# CANTensegrityBoard.net
KiCad netlist of a schematic drawn in EAGLE
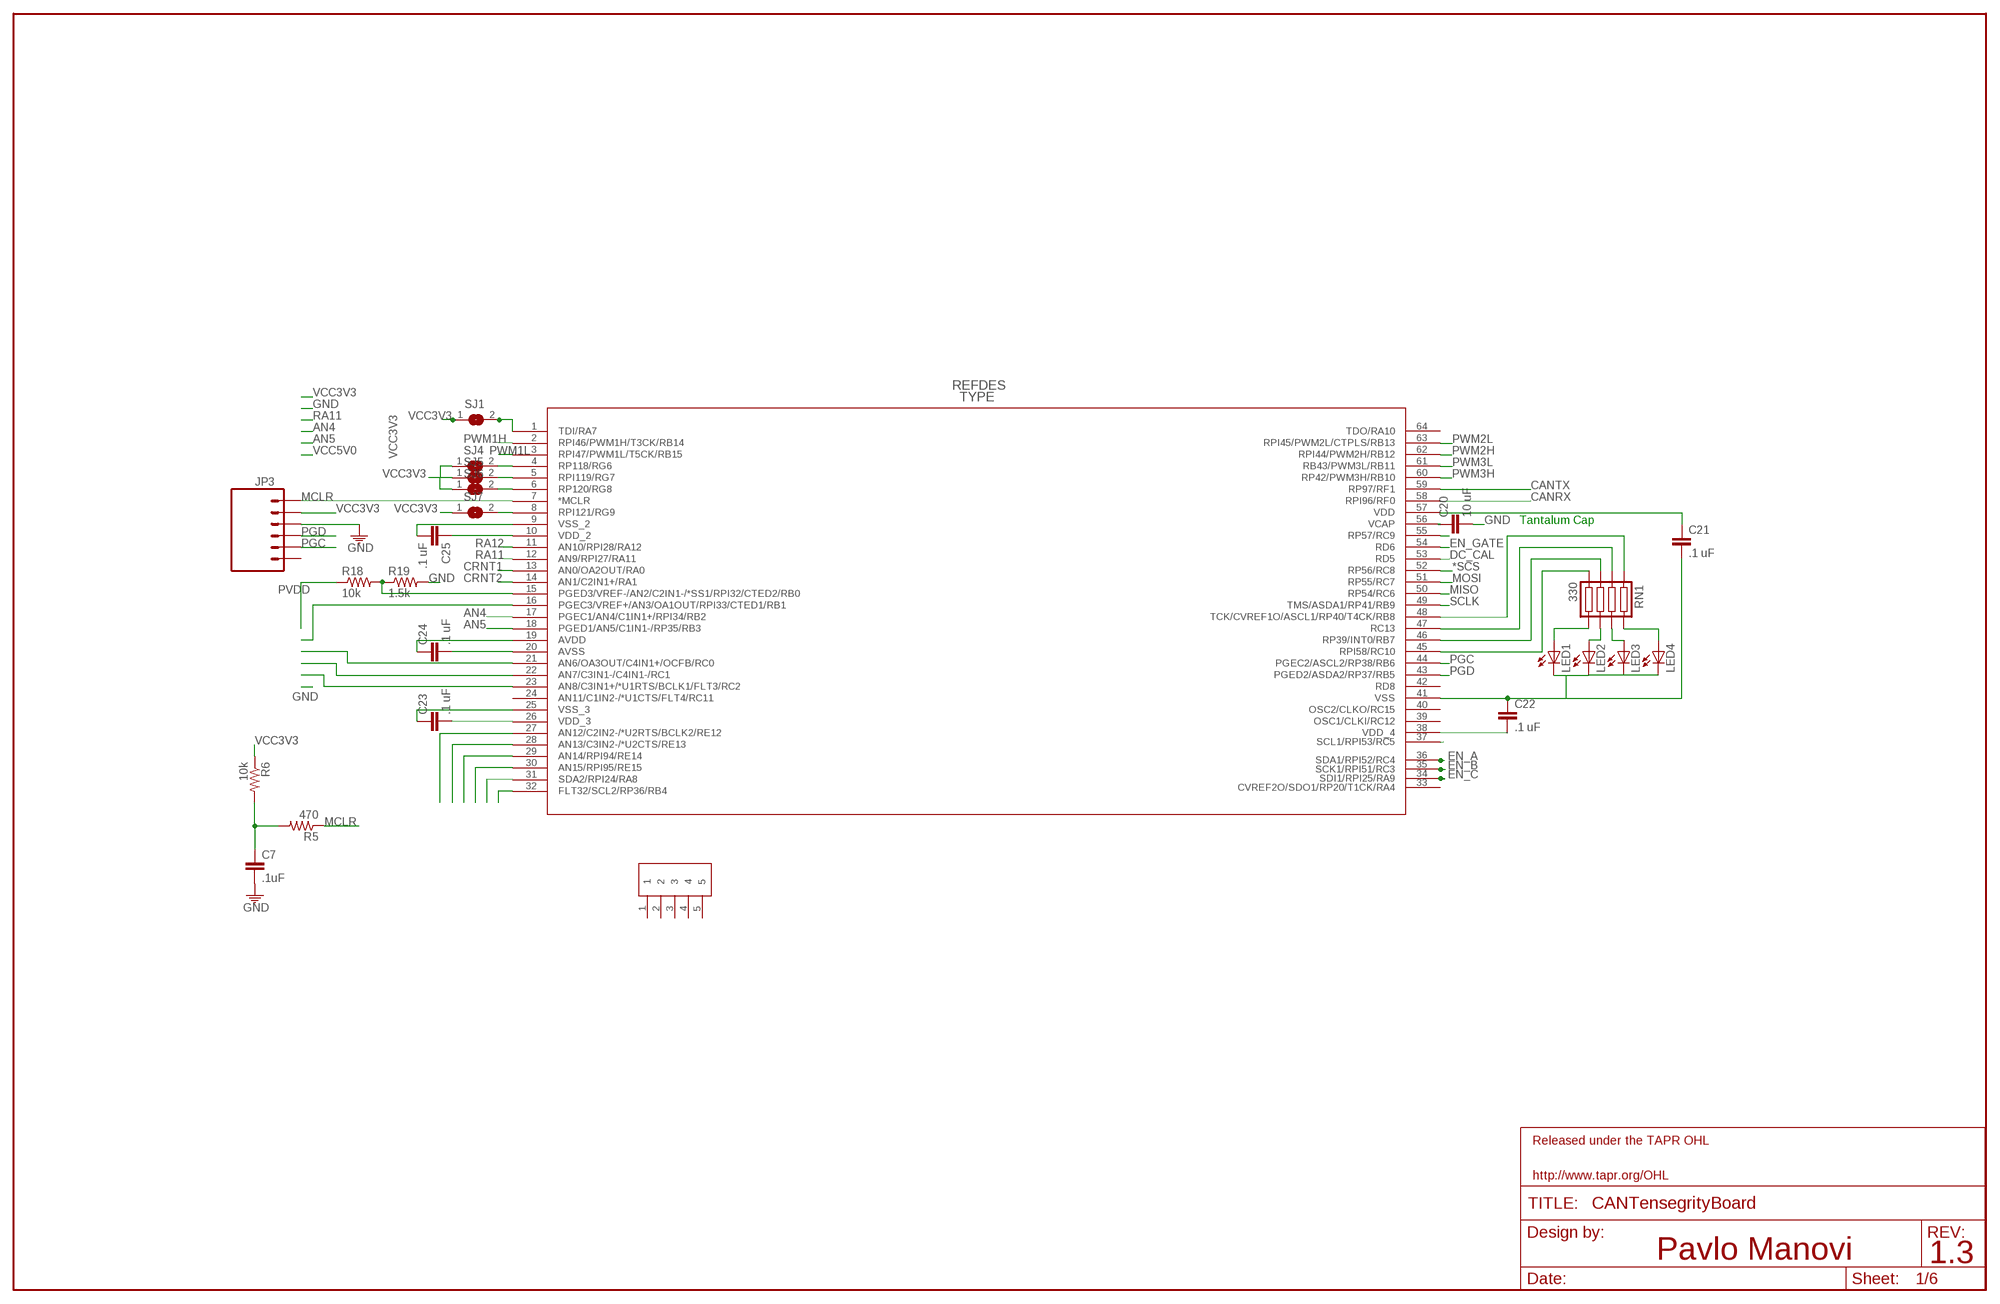
[diagram p0: schematic, sheet 1]
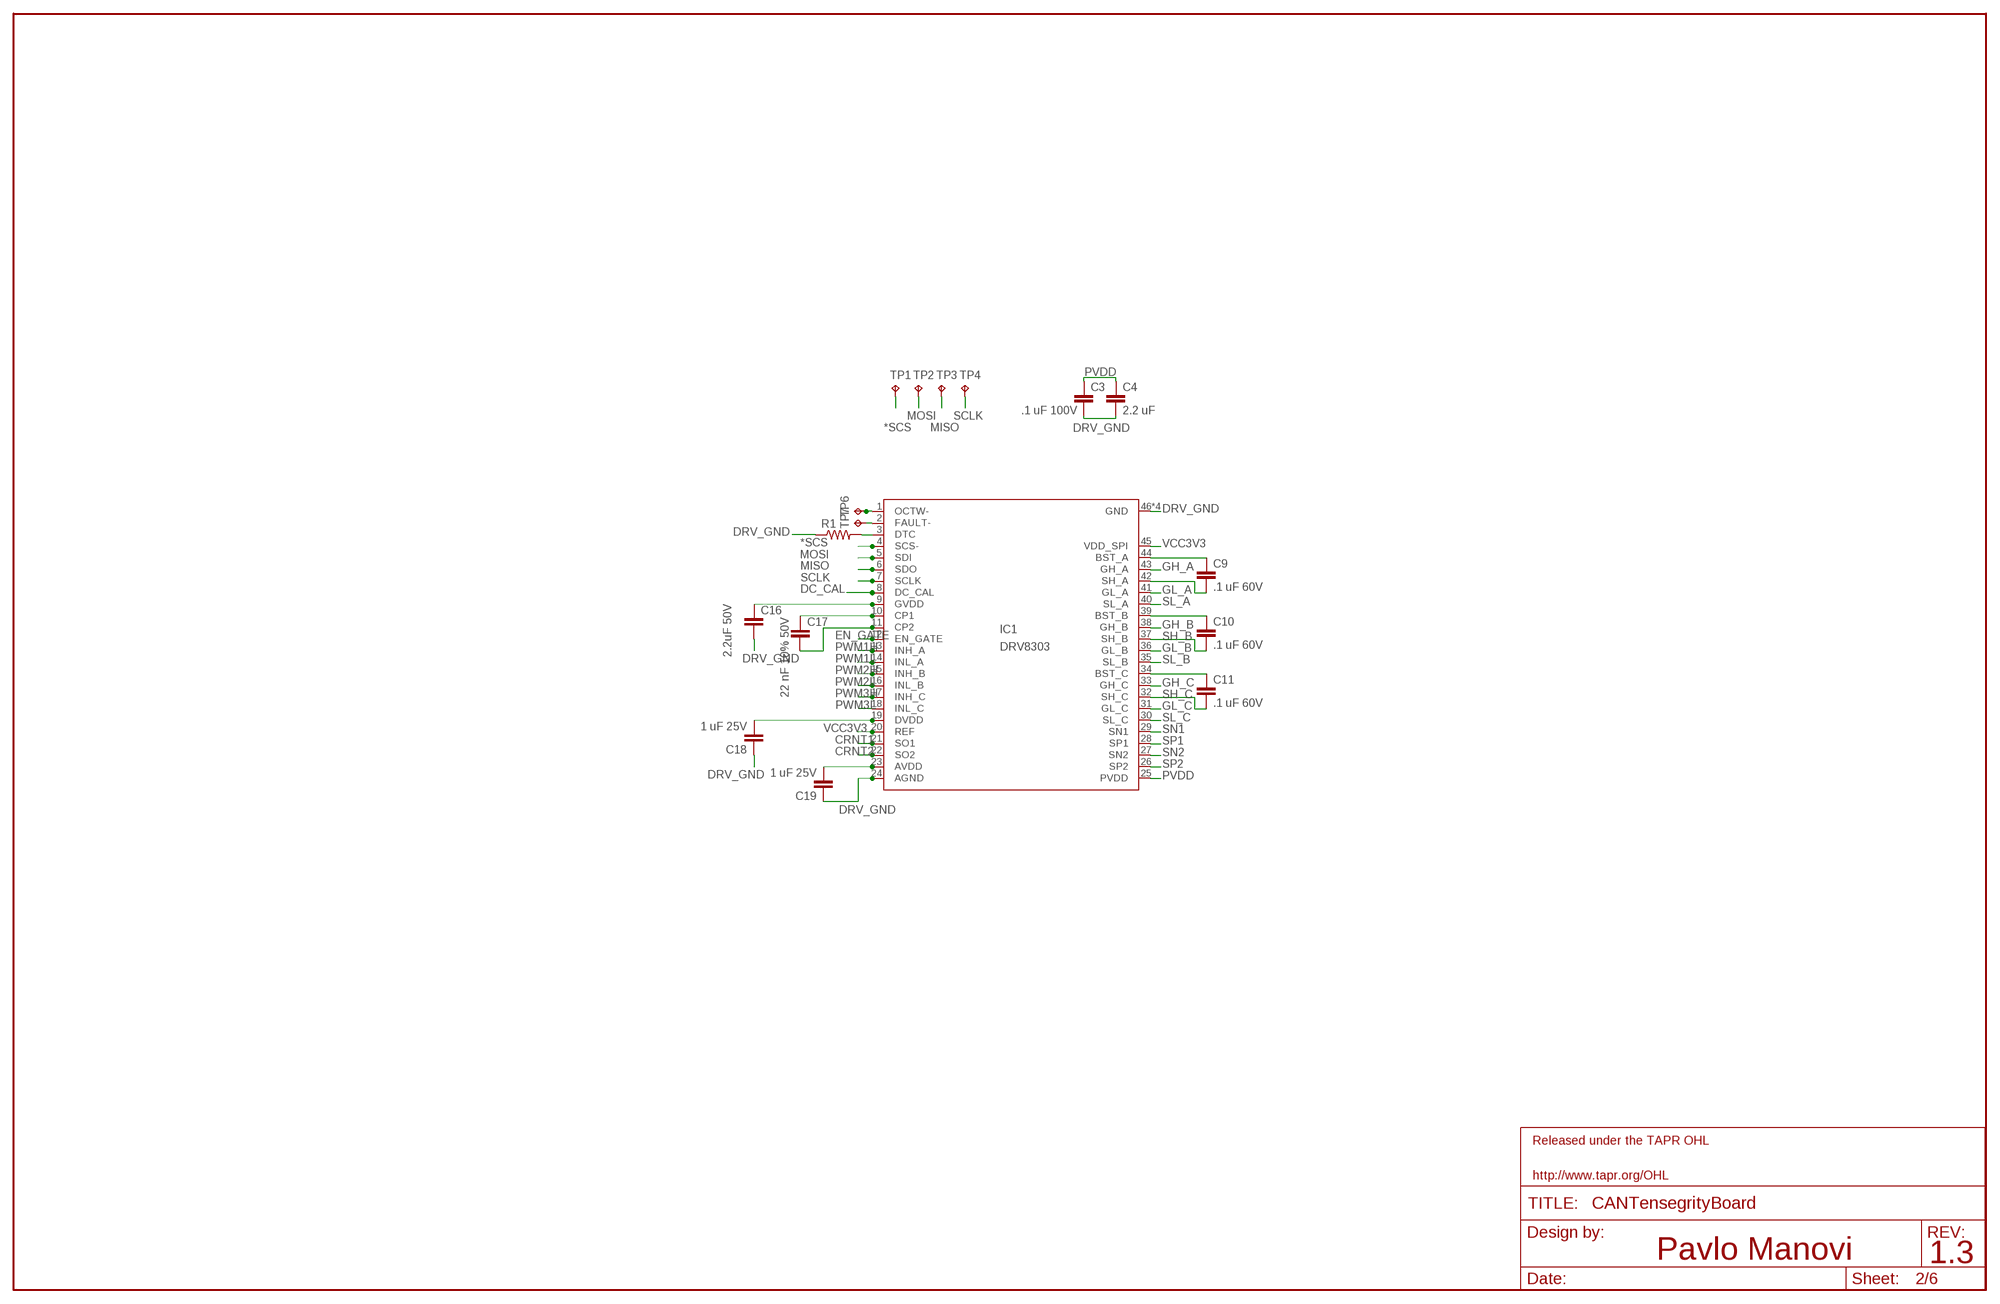
[diagram p1: schematic, sheet 2]
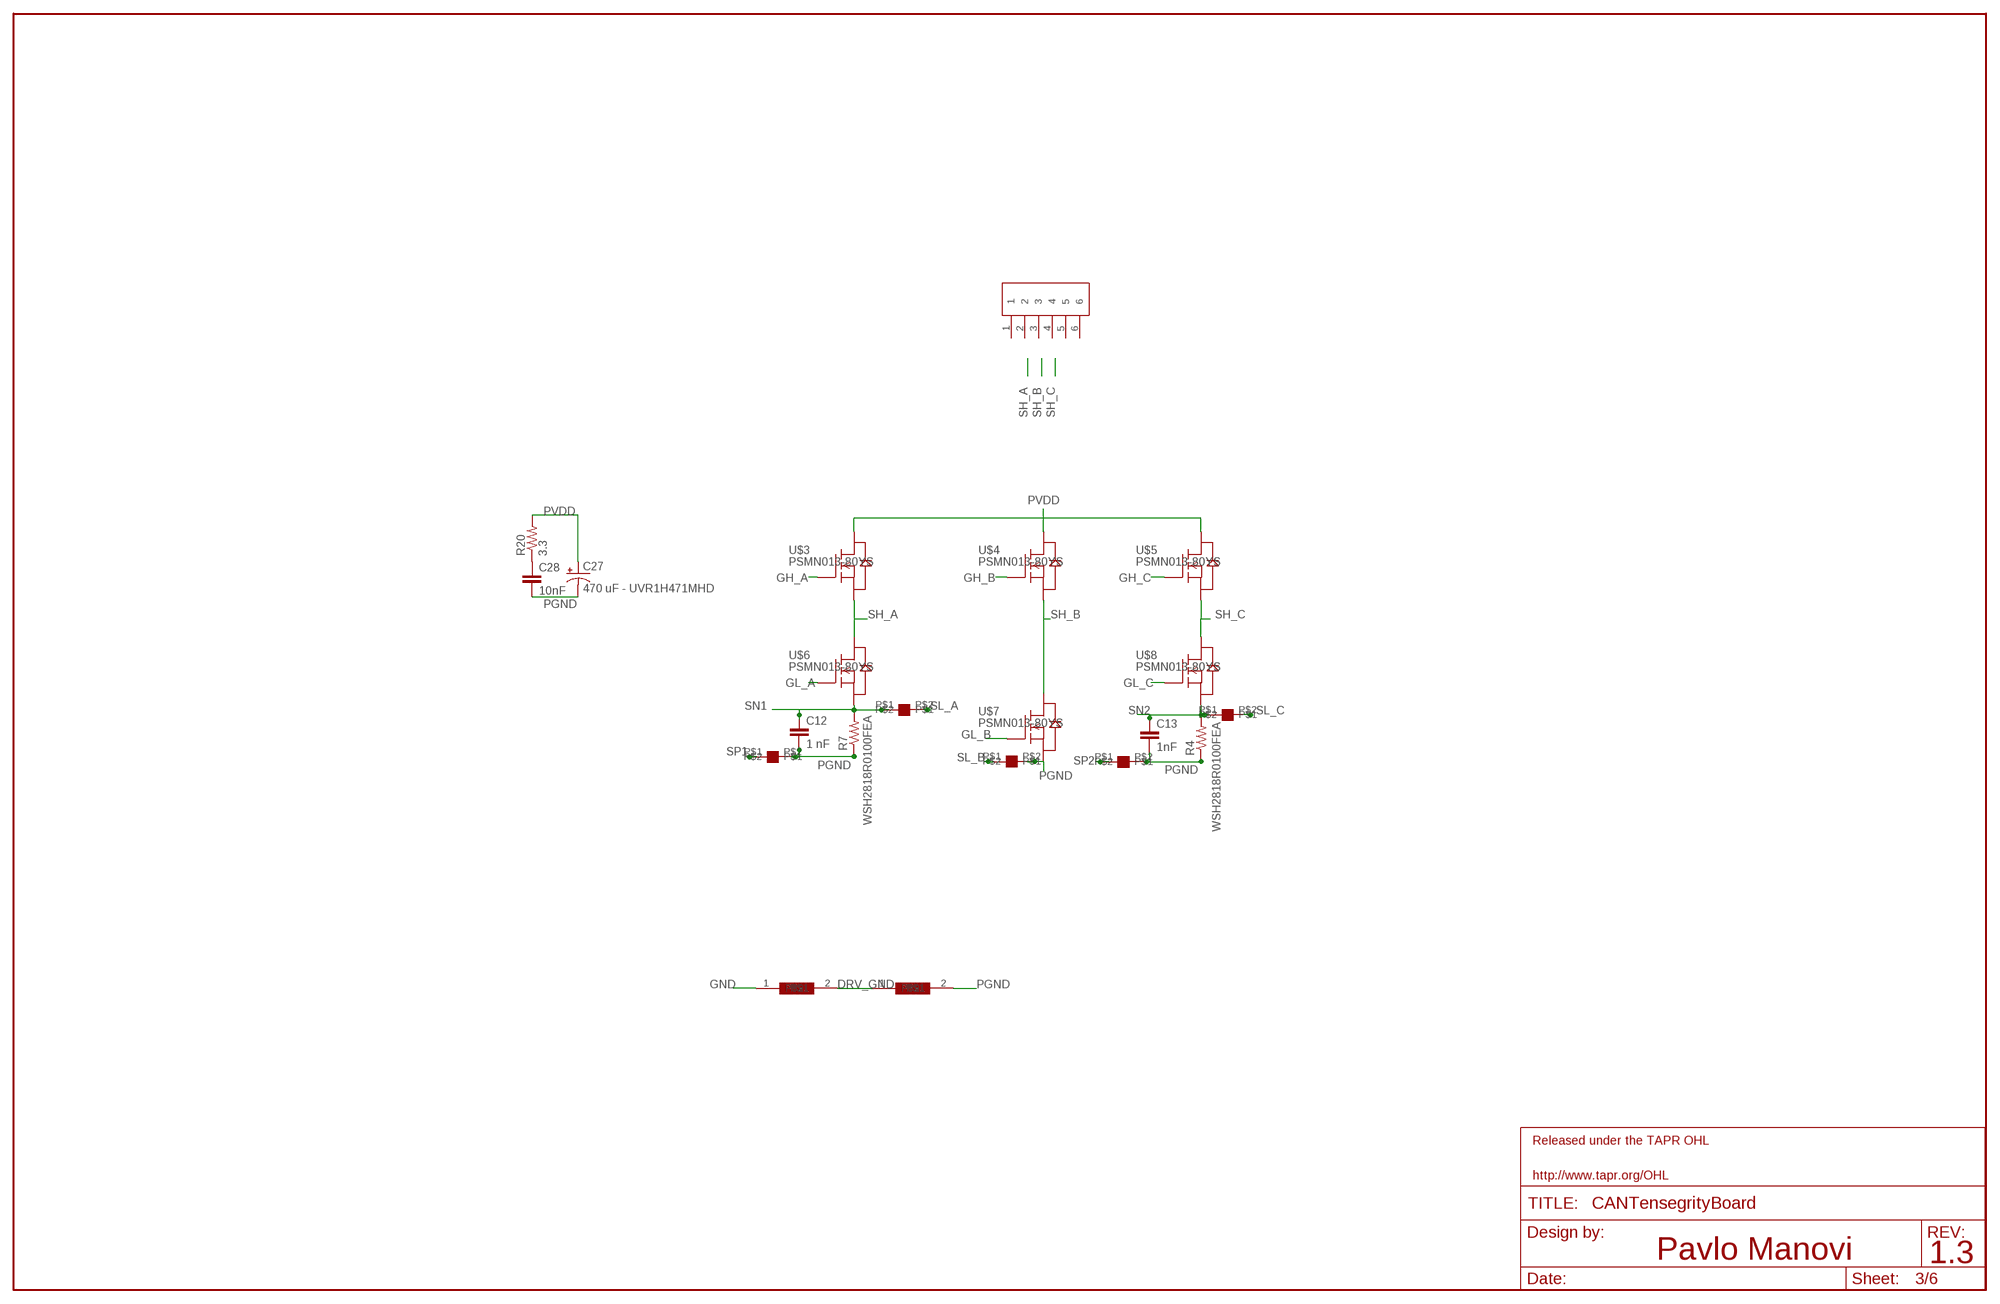
[diagram p2: schematic, sheet 3]
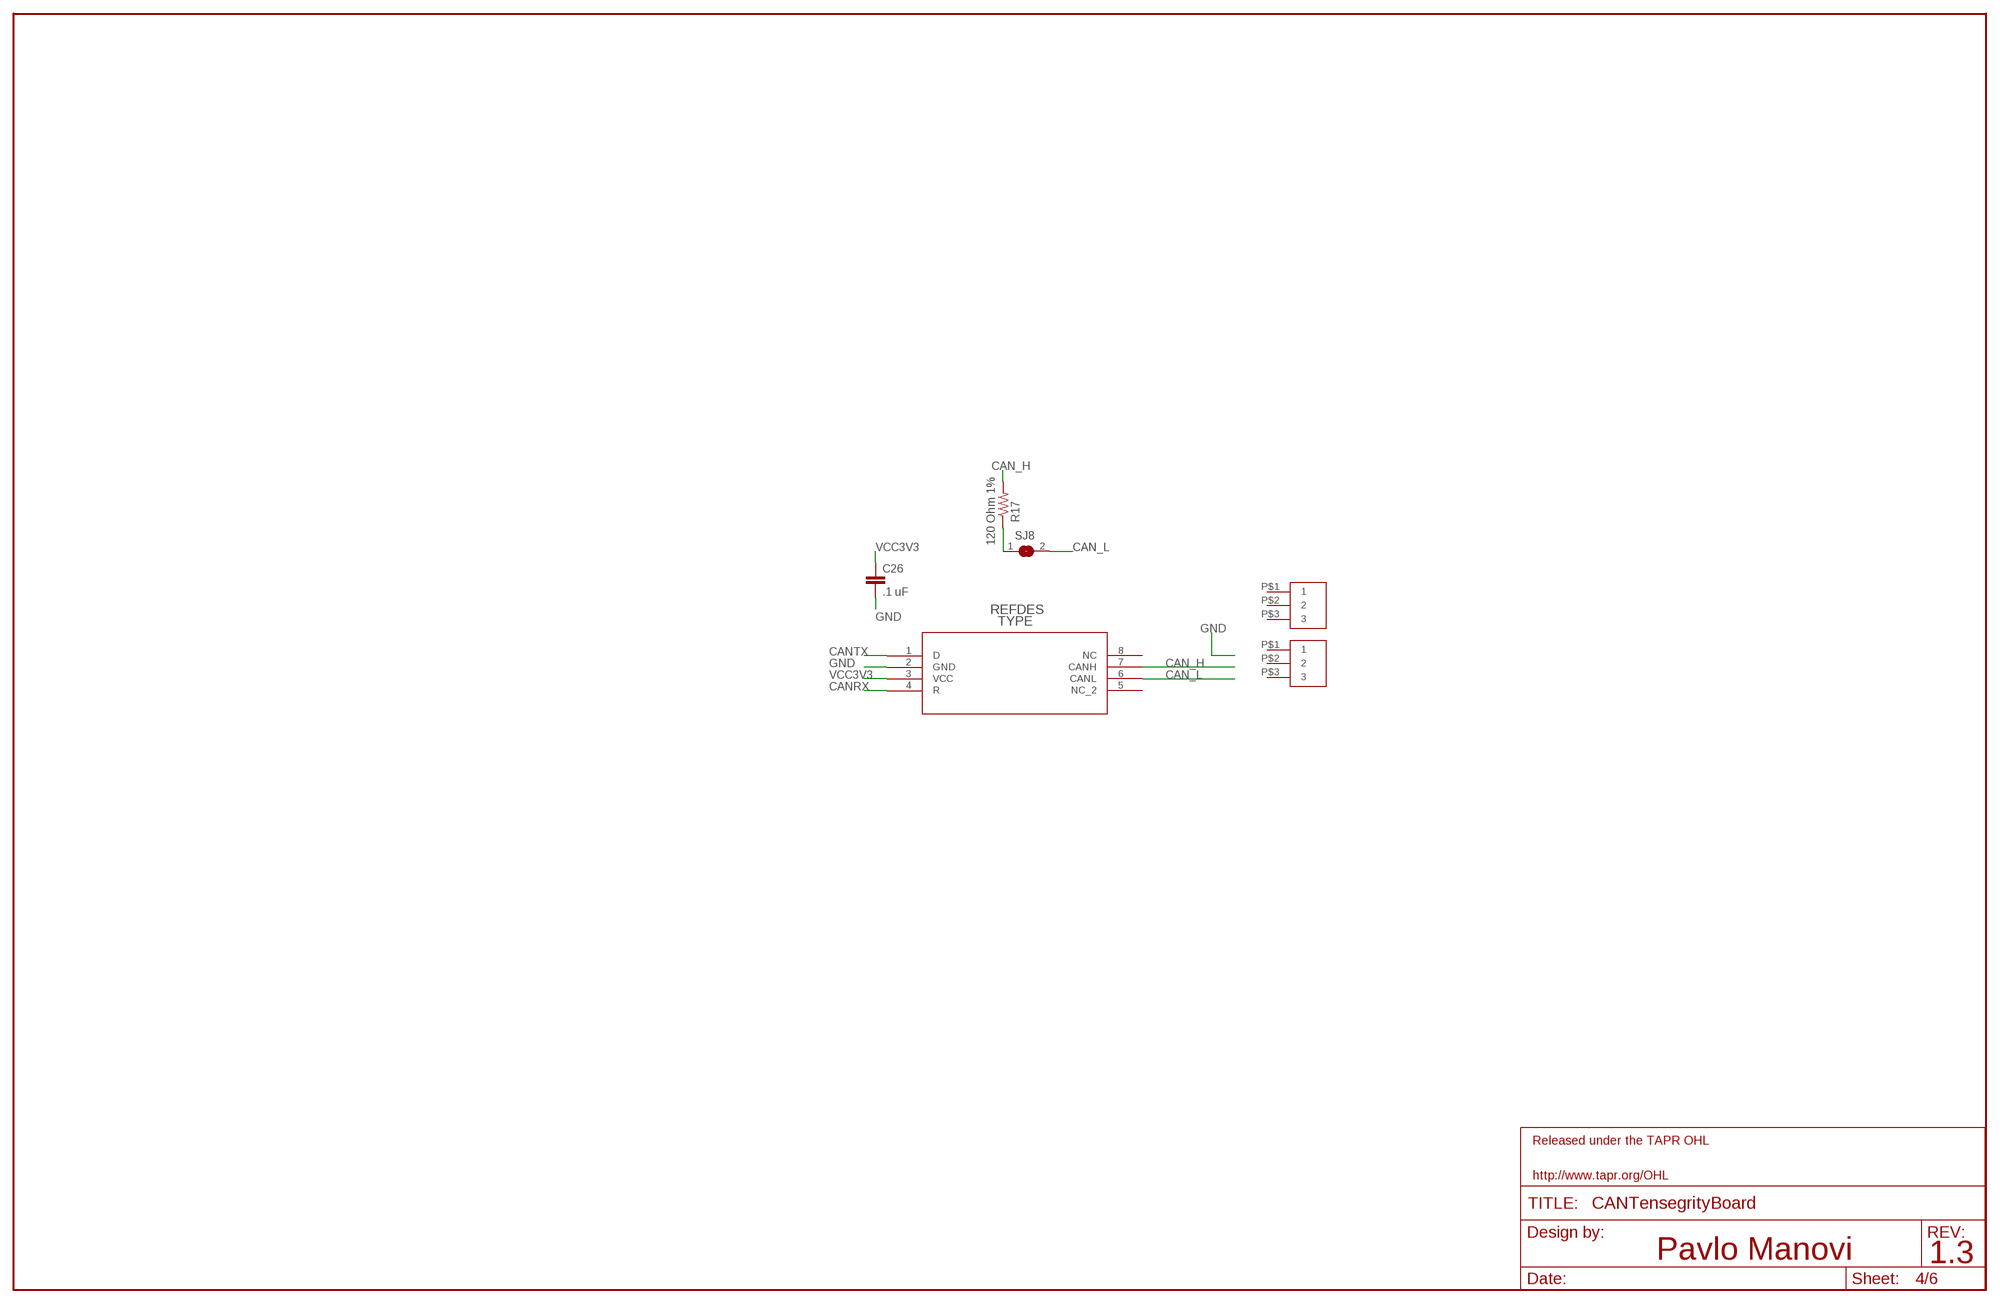
[diagram p3: schematic, sheet 4]
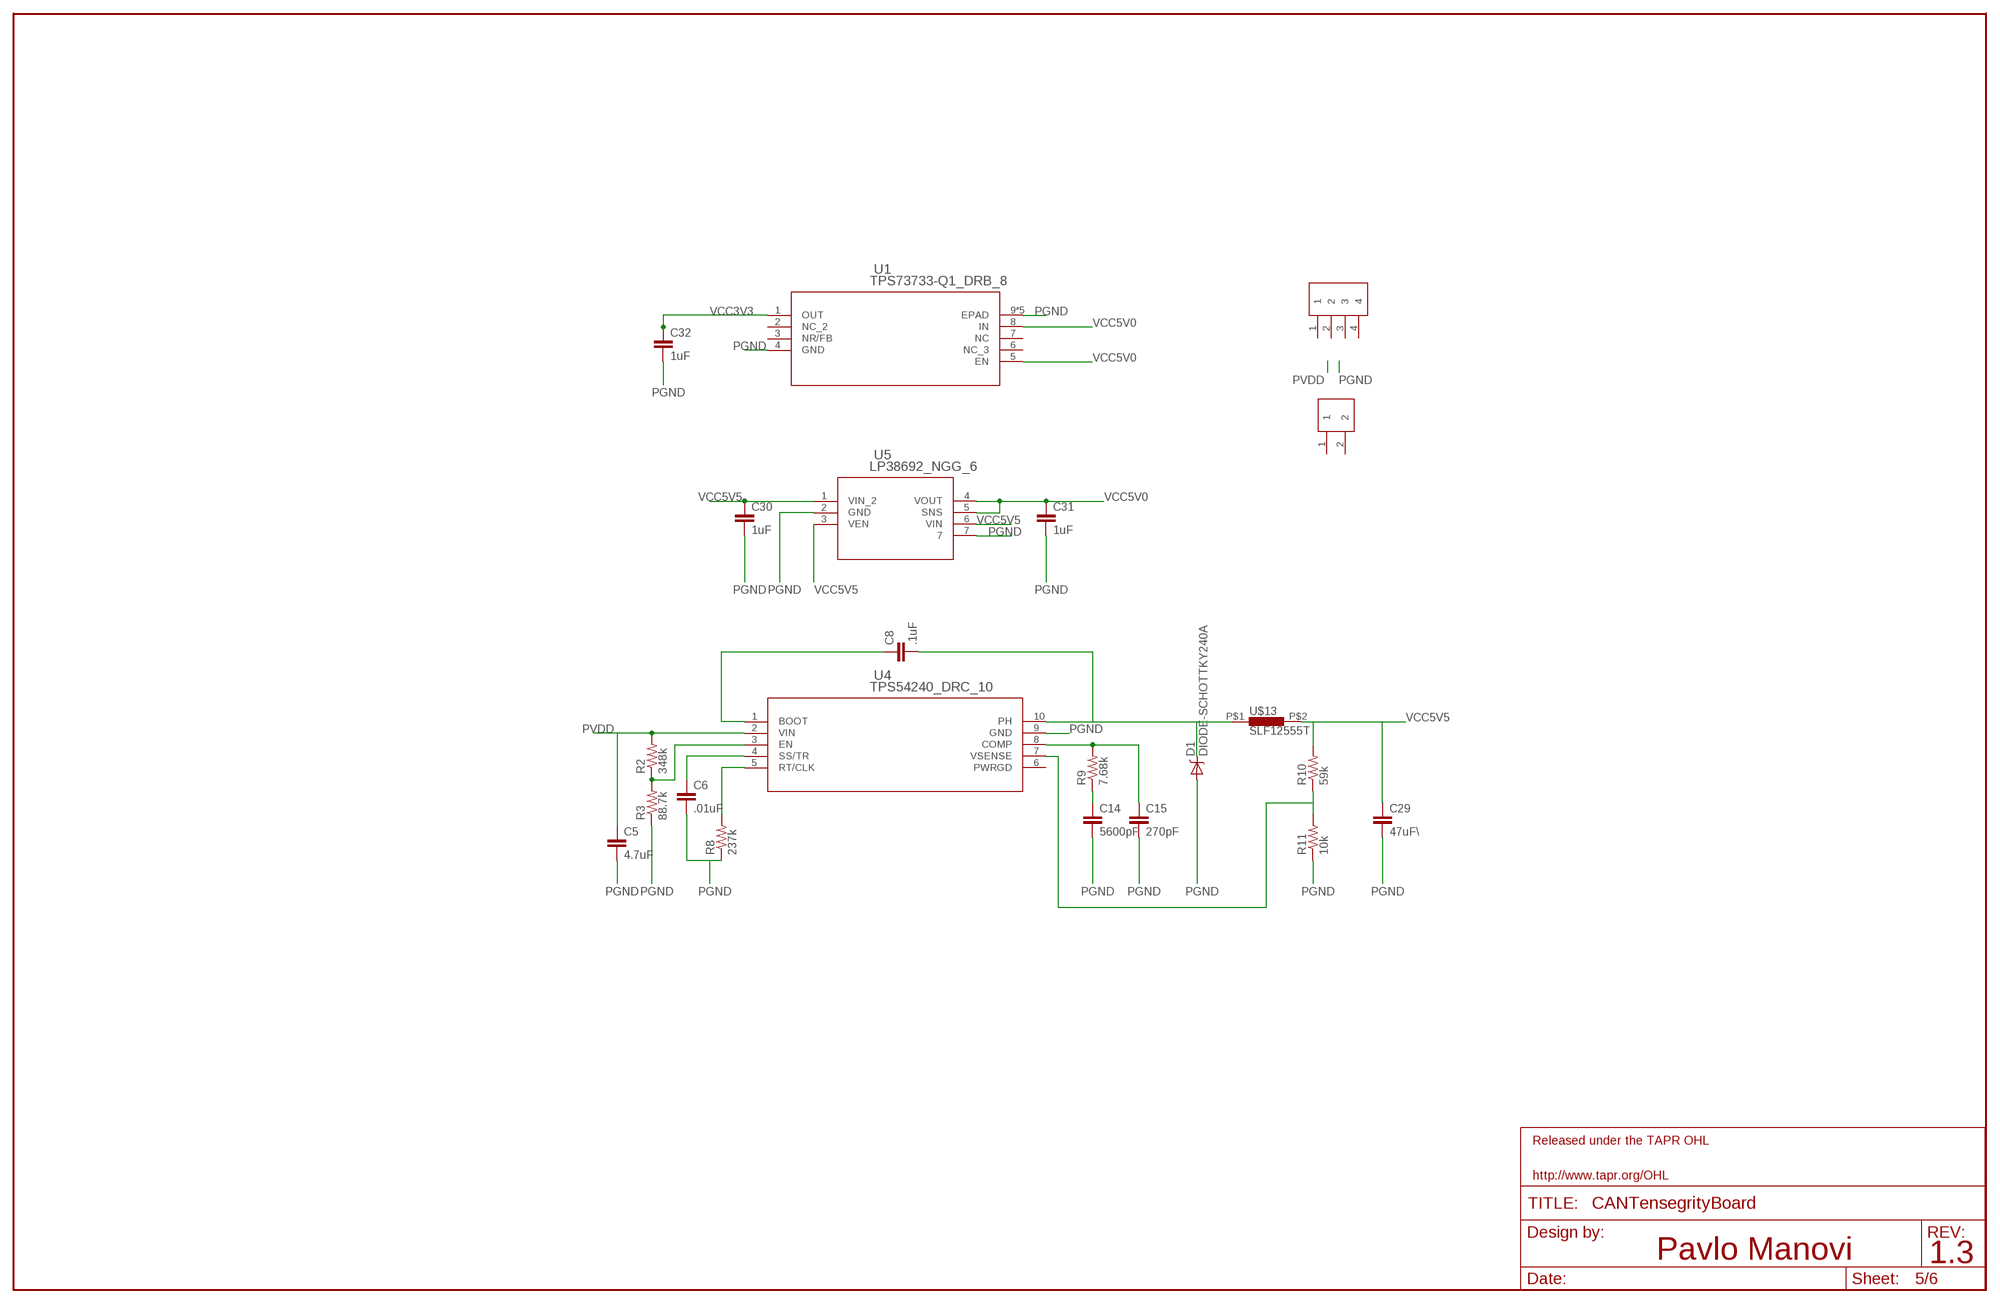
[diagram p4: schematic, sheet 5]
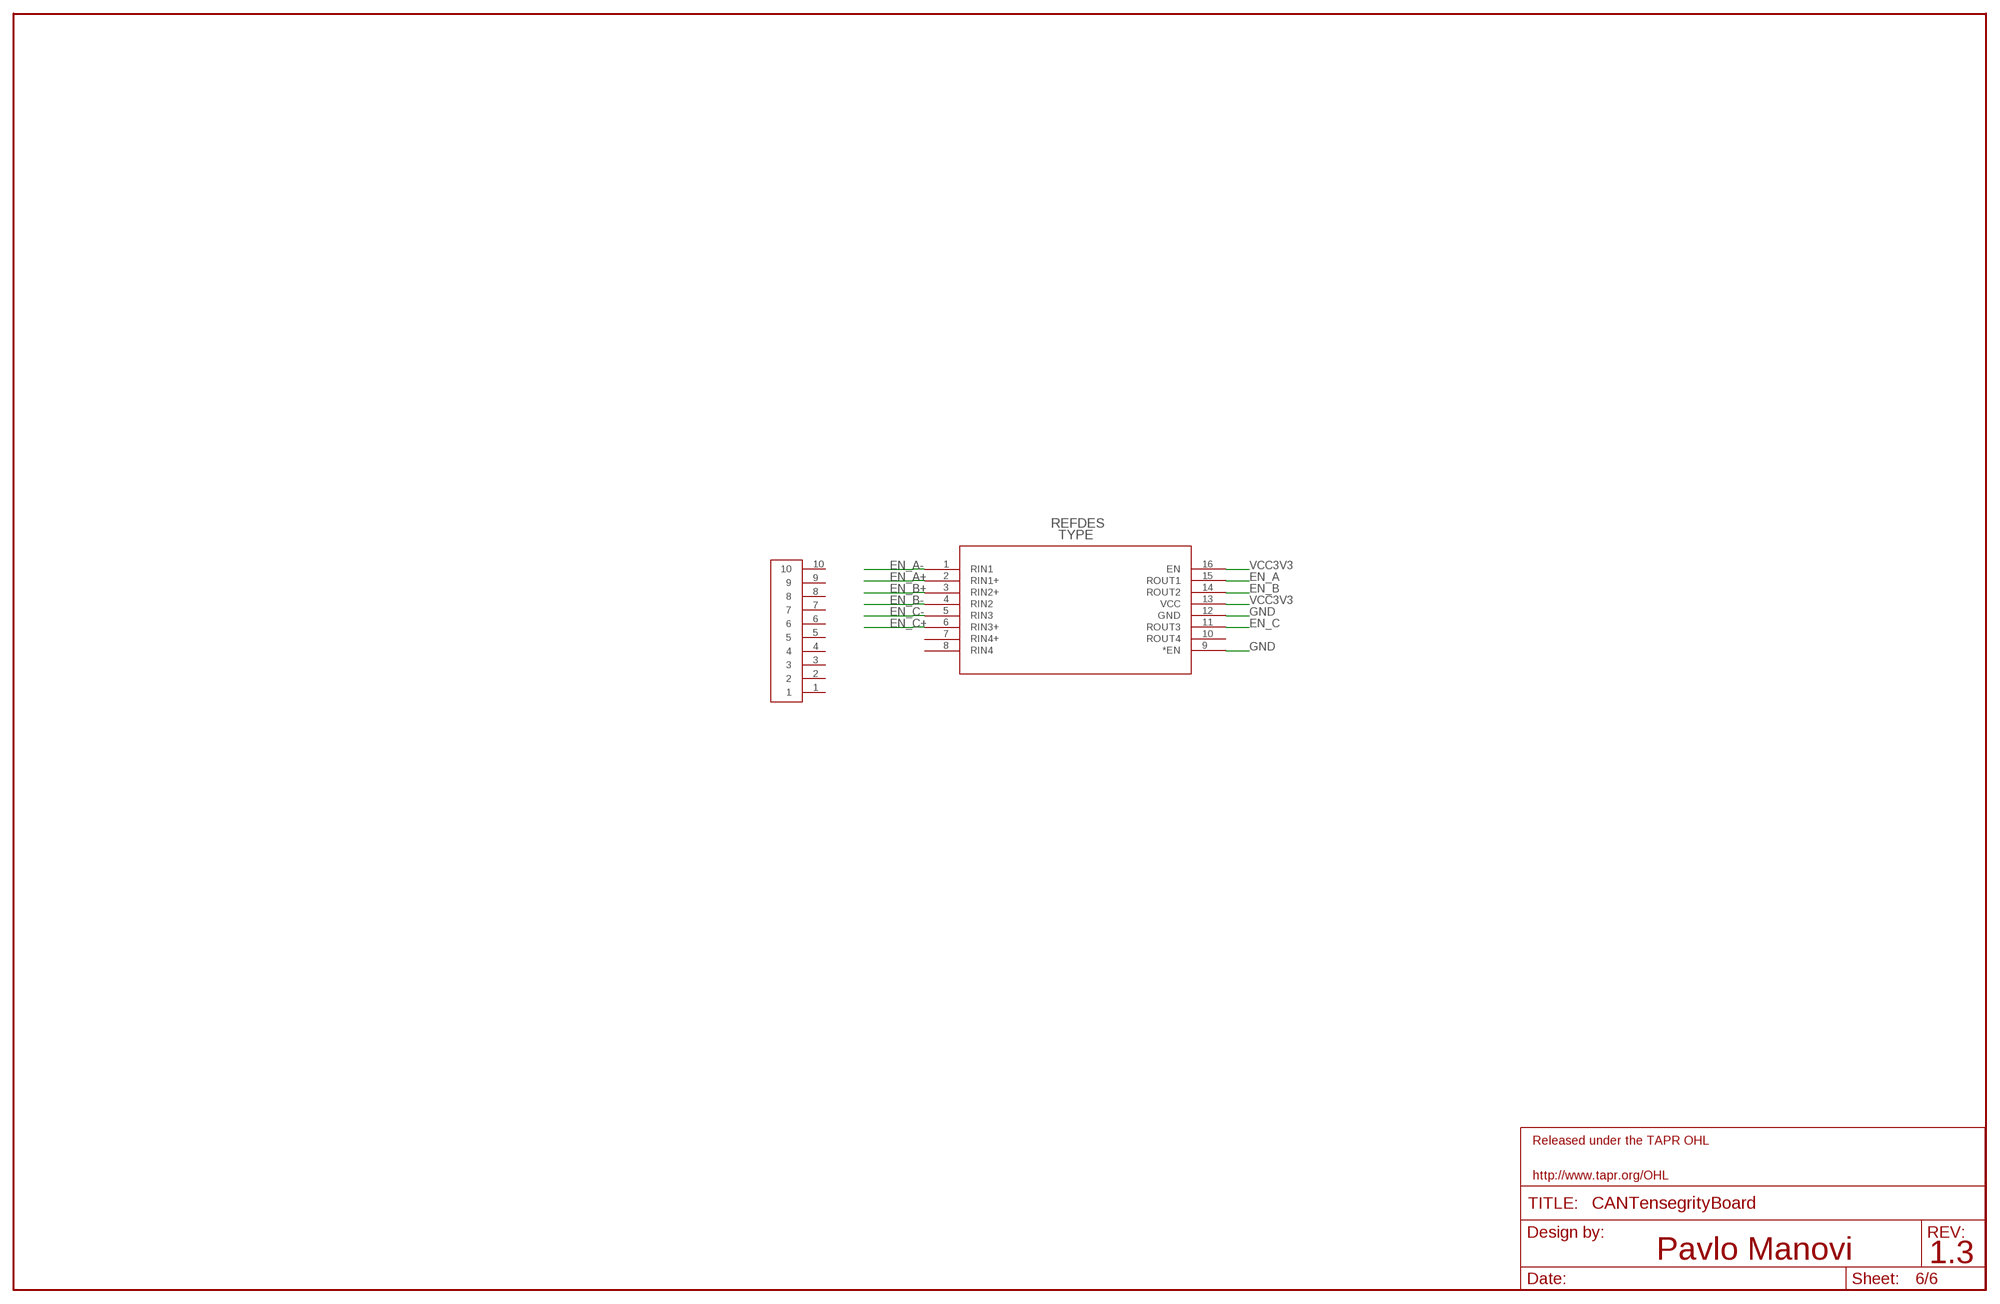
[diagram p5: schematic, sheet 6]

(export (version "E")
  (design (tool "Eeschema 10.0.6"))
  (components
    (comp (ref "C3")
      (value ".1 uF 100V")
      (footprint "eagle-import:0805")
      (libsource (lib "eagle-import") (part "CAP0805"))
    )
    (comp (ref "C4")
      (value "2.2 uF")
      (footprint "eagle-import:0805")
      (libsource (lib "eagle-import") (part "CAP0805"))
    )
    (comp (ref "C9")
      (value ".1 uF 60V")
      (footprint "eagle-import:0805")
      (libsource (lib "eagle-import") (part "CAP0805"))
    )
    (comp (ref "C10")
      (value ".1 uF 60V")
      (footprint "eagle-import:0805")
      (libsource (lib "eagle-import") (part "CAP0805"))
    )
    (comp (ref "C11")
      (value ".1 uF 60V")
      (footprint "eagle-import:0805")
      (libsource (lib "eagle-import") (part "CAP0805"))
    )
    (comp (ref "C16")
      (value "2.2uF 50V")
      (footprint "eagle-import:1206")
      (libsource (lib "eagle-import") (part "CAP1206"))
    )
    (comp (ref "C17")
      (value "22 nF 10% 50V")
      (footprint "eagle-import:0805")
      (libsource (lib "eagle-import") (part "CAP0805"))
    )
    (comp (ref "C18")
      (value "1 uF 25V")
      (footprint "eagle-import:0805")
      (libsource (lib "eagle-import") (part "CAP0805"))
    )
    (comp (ref "C19")
      (value "1 uF 25V")
      (footprint "eagle-import:0805")
      (libsource (lib "eagle-import") (part "CAP0805"))
    )
    (comp (ref "IC1")
      (value "DRV8303")
      (footprint "eagle-import:HTSSOP-480-DCA")
      (libsource (lib "eagle-import") (part "DRV8303"))
    )
    (comp (ref "R1")
      (value "RESISTOR0805-RES")
      (footprint "eagle-import:0805")
      (libsource (lib "eagle-import") (part "RESISTOR0805-RES"))
    )
    (comp (ref "TP1")
      (value "TPTP06R")
      (footprint "eagle-import:TP06R")
      (libsource (lib "eagle-import") (part "TPTP06R"))
    )
    (comp (ref "TP2")
      (value "TPTP06R")
      (footprint "eagle-import:TP06R")
      (libsource (lib "eagle-import") (part "TPTP06R"))
    )
    (comp (ref "TP3")
      (value "TPTP06R")
      (footprint "eagle-import:TP06R")
      (libsource (lib "eagle-import") (part "TPTP06R"))
    )
    (comp (ref "TP4")
      (value "TPTP06R")
      (footprint "eagle-import:TP06R")
      (libsource (lib "eagle-import") (part "TPTP06R"))
    )
    (comp (ref "TP6")
      (value "TPTP06R")
      (footprint "eagle-import:TP06R")
      (libsource (lib "eagle-import") (part "TPTP06R"))
    )
    (comp (ref "TP7")
      (value "TPTP06R")
      (footprint "eagle-import:TP06R")
      (libsource (lib "eagle-import") (part "TPTP06R"))
    )
    (comp (ref "U$15")
      (value "3M10PIN2500")
      (footprint "eagle-import:FOUR-WALL-2500-LP-STH")
      (libsource (lib "eagle-import") (part "3M10PIN2500"))
    )
    (comp (ref "U3")
      (value "SN65LVDT348_PW_1")
      (footprint "eagle-import:PW16")
      (libsource (lib "eagle-import") (part "SN65LVDT348_PW_1"))
    )
    (comp (ref "C26")
      (value ".1 uF")
      (footprint "eagle-import:0805")
      (libsource (lib "eagle-import") (part "CAP0805"))
    )
    (comp (ref "R17")
      (value "120 Ohm 1%")
      (footprint "eagle-import:0805")
      (libsource (lib "eagle-import") (part "RESISTOR0805-RES"))
    )
    (comp (ref "SJ8") (value "SJ") (footprint "eagle-import:SJ") (libsource (lib "eagle-import") (part "SJ")))
    (comp (ref "U$14")
      (value "MICROCLASP3")
      (footprint "eagle-import:55932-0310")
      (libsource (lib "eagle-import") (part "MICROCLASP3"))
    )
    (comp (ref "U$19")
      (value "MICROCLASP3")
      (footprint "eagle-import:55932-0310")
      (libsource (lib "eagle-import") (part "MICROCLASP3"))
    )
    (comp (ref "U2")
      (value "SN65HVD232_D_8")
      (footprint "eagle-import:D8")
      (libsource (lib "eagle-import") (part "SN65HVD232_D_8"))
    )
    (comp (ref "C12")
      (value "1 nF")
      (footprint "eagle-import:0805")
      (libsource (lib "eagle-import") (part "CAP0805"))
    )
    (comp (ref "C13")
      (value "1nF")
      (footprint "eagle-import:0805")
      (libsource (lib "eagle-import") (part "CAP0805"))
    )
    (comp (ref "C27")
      (value "470 uF - UVR1H471MHD")
      (footprint "eagle-import:CPOL-RADIAL-1000UF-25V")
      (libsource (lib "eagle-import") (part "CAP_POLPTH4"))
    )
    (comp (ref "C28")
      (value "10nF")
      (footprint "eagle-import:0805")
      (libsource (lib "eagle-import") (part "CAP0805"))
    )
    (comp (ref "R4")
      (value "WSH2818R0100FEA")
      (footprint "eagle-import:SMT-REF")
      (libsource (lib "eagle-import") (part "RESISTOR"))
    )
    (comp (ref "R7")
      (value "WSH2818R0100FEA")
      (footprint "eagle-import:SMT-REF")
      (libsource (lib "eagle-import") (part "RESISTOR"))
    )
    (comp (ref "R20")
      (value "3.3")
      (footprint "eagle-import:0805")
      (libsource (lib "eagle-import") (part "RESISTOR0805-RES"))
    )
    (comp (ref "U$2")
      (value "NETJUMPER")
      (footprint "eagle-import:NETJUMPER")
      (libsource (lib "eagle-import") (part "NETJUMPER"))
    )
    (comp (ref "U$3")
      (value "PSMN013-80YS")
      (footprint "eagle-import:TO127P600X120-5N")
      (libsource (lib "eagle-import") (part "PSMN013-80YS"))
    )
    (comp (ref "U$4")
      (value "PSMN013-80YS")
      (footprint "eagle-import:TO127P600X120-5N")
      (libsource (lib "eagle-import") (part "PSMN013-80YS"))
    )
    (comp (ref "U$5")
      (value "PSMN013-80YS")
      (footprint "eagle-import:TO127P600X120-5N")
      (libsource (lib "eagle-import") (part "PSMN013-80YS"))
    )
    (comp (ref "U$6")
      (value "PSMN013-80YS")
      (footprint "eagle-import:TO127P600X120-5N")
      (libsource (lib "eagle-import") (part "PSMN013-80YS"))
    )
    (comp (ref "U$7")
      (value "PSMN013-80YS")
      (footprint "eagle-import:TO127P600X120-5N")
      (libsource (lib "eagle-import") (part "PSMN013-80YS"))
    )
    (comp (ref "U$8")
      (value "PSMN013-80YS")
      (footprint "eagle-import:TO127P600X120-5N")
      (libsource (lib "eagle-import") (part "PSMN013-80YS"))
    )
    (comp (ref "U$9")
      (value "NETJUMPER")
      (footprint "eagle-import:NETJUMPER")
      (libsource (lib "eagle-import") (part "NETJUMPER"))
    )
    (comp (ref "U$10")
      (value "NETJUMPER")
      (footprint "eagle-import:NETJUMPER")
      (libsource (lib "eagle-import") (part "NETJUMPER"))
    )
    (comp (ref "U$11")
      (value "NETJUMPER")
      (footprint "eagle-import:NETJUMPER")
      (libsource (lib "eagle-import") (part "NETJUMPER"))
    )
    (comp (ref "U$12")
      (value "NETJUMPER")
      (footprint "eagle-import:NETJUMPER")
      (libsource (lib "eagle-import") (part "NETJUMPER"))
    )
    (comp (ref "U$17")
      (value "MINIFITJR6PIN")
      (footprint "eagle-import:0039288060")
      (libsource (lib "eagle-import") (part "MINIFITJR6PIN"))
    )
    (comp (ref "U9")
      (value "H1206T500R-10")
      (footprint "eagle-import:1206")
      (libsource (lib "eagle-import") (part "H1206T500R-10"))
    )
    (comp (ref "U10")
      (value "H1206T500R-10")
      (footprint "eagle-import:1206")
      (libsource (lib "eagle-import") (part "H1206T500R-10"))
    )
    (comp (ref "C7")
      (value ".1uF")
      (footprint "eagle-import:0805")
      (libsource (lib "eagle-import") (part "CAP0805"))
    )
    (comp (ref "C20")
      (value "10 uF")
      (footprint "eagle-import:1206")
      (libsource (lib "eagle-import") (part "CAP1206"))
    )
    (comp (ref "C21")
      (value ".1 uF")
      (footprint "eagle-import:0805")
      (libsource (lib "eagle-import") (part "CAP0805"))
    )
    (comp (ref "C22")
      (value ".1 uF")
      (footprint "eagle-import:0805")
      (libsource (lib "eagle-import") (part "CAP0805"))
    )
    (comp (ref "C23")
      (value ".1 uF")
      (footprint "eagle-import:0805")
      (libsource (lib "eagle-import") (part "CAP0805"))
    )
    (comp (ref "C24")
      (value ".1 uF")
      (footprint "eagle-import:0805")
      (libsource (lib "eagle-import") (part "CAP0805"))
    )
    (comp (ref "C25")
      (value ".1 uF")
      (footprint "eagle-import:0805")
      (libsource (lib "eagle-import") (part "CAP0805"))
    )
    (comp (ref "JP3")
      (value "M06LOCK")
      (footprint "eagle-import:1X06_LOCK")
      (libsource (lib "eagle-import") (part "M06LOCK"))
    )
    (comp (ref "LED1")
      (value "LED0805")
      (footprint "eagle-import:LED-0805")
      (libsource (lib "eagle-import") (part "LED0805"))
    )
    (comp (ref "LED2")
      (value "LED0805")
      (footprint "eagle-import:LED-0805")
      (libsource (lib "eagle-import") (part "LED0805"))
    )
    (comp (ref "LED3")
      (value "LED0805")
      (footprint "eagle-import:LED-0805")
      (libsource (lib "eagle-import") (part "LED0805"))
    )
    (comp (ref "LED4")
      (value "LED0805")
      (footprint "eagle-import:LED-0805")
      (libsource (lib "eagle-import") (part "LED0805"))
    )
    (comp (ref "R5")
      (value "470")
      (footprint "eagle-import:0805")
      (libsource (lib "eagle-import") (part "CMPE118lib_RESISTOR0805-RES"))
    )
    (comp (ref "R6")
      (value "10k")
      (footprint "eagle-import:0805")
      (libsource (lib "eagle-import") (part "CMPE118lib_RESISTOR0805-RES"))
    )
    (comp (ref "R18")
      (value "10k")
      (footprint "eagle-import:0805")
      (libsource (lib "eagle-import") (part "RESISTOR0805-RES"))
    )
    (comp (ref "R19")
      (value "1.5k")
      (footprint "eagle-import:0805")
      (libsource (lib "eagle-import") (part "RESISTOR0805-RES"))
    )
    (comp (ref "RN1")
      (value "330")
      (footprint "eagle-import:EXB-38V271JV")
      (libsource (lib "eagle-import") (part "RESISTOR_ARRAY-4"))
    )
    (comp (ref "SJ1") (value "SJ") (footprint "eagle-import:SJ") (libsource (lib "eagle-import") (part "SJ")))
    (comp (ref "SJ4") (value "SJ") (footprint "eagle-import:SJ") (libsource (lib "eagle-import") (part "SJ")))
    (comp (ref "SJ5") (value "SJ") (footprint "eagle-import:SJ") (libsource (lib "eagle-import") (part "SJ")))
    (comp (ref "SJ6") (value "SJ") (footprint "eagle-import:SJ") (libsource (lib "eagle-import") (part "SJ")))
    (comp (ref "SJ7") (value "SJ") (footprint "eagle-import:SJ") (libsource (lib "eagle-import") (part "SJ")))
    (comp (ref "U$1")
      (value "DSPIC33EP128MC502-I/SS")
      (footprint "eagle-import:QFP64-10X10MC")
      (libsource (lib "eagle-import") (part "DSPIC33EP256MC50"))
    )
    (comp (ref "U$20")
      (value "MICROCLASP5")
      (footprint "eagle-import:55932-0510")
      (libsource (lib "eagle-import") (part "MICROCLASP5"))
    )
    (comp (ref "C5")
      (value "4.7uF")
      (footprint "eagle-import:1210")
      (libsource (lib "eagle-import") (part "SwitcherPowerStage_CAP1210"))
    )
    (comp (ref "C6")
      (value ".01uF")
      (footprint "eagle-import:0805")
      (libsource (lib "eagle-import") (part "SwitcherPowerStage_CAP0805"))
    )
    (comp (ref "C8")
      (value ".1uF")
      (footprint "eagle-import:0805")
      (libsource (lib "eagle-import") (part "SwitcherPowerStage_CAP0805"))
    )
    (comp (ref "C14")
      (value "5600pF")
      (footprint "eagle-import:0805")
      (libsource (lib "eagle-import") (part "SwitcherPowerStage_CAP0805"))
    )
    (comp (ref "C15")
      (value "270pF")
      (footprint "eagle-import:0805")
      (libsource (lib "eagle-import") (part "SwitcherPowerStage_CAP0805"))
    )
    (comp (ref "C29")
      (value "47uF\\")
      (footprint "eagle-import:C2220K")
      (libsource (lib "eagle-import") (part "CAP"))
    )
    (comp (ref "C30")
      (value "1uF")
      (footprint "eagle-import:0805")
      (libsource (lib "eagle-import") (part "SwitcherPowerStage_CAP0805"))
    )
    (comp (ref "C31")
      (value "1uF")
      (footprint "eagle-import:0805")
      (libsource (lib "eagle-import") (part "SwitcherPowerStage_CAP0805"))
    )
    (comp (ref "C32")
      (value "1uF")
      (footprint "eagle-import:0805")
      (libsource (lib "eagle-import") (part "SwitcherPowerStage_CAP0805"))
    )
    (comp (ref "D1")
      (value "DIODE-SCHOTTKY240A")
      (footprint "eagle-import:SMA-DIODE-B240A")
      (libsource (lib "eagle-import") (part "DIODE-SCHOTTKY240A"))
    )
    (comp (ref "R2")
      (value "348k")
      (footprint "eagle-import:0805")
      (libsource (lib "eagle-import") (part "SwitcherPowerStage_RESISTOR0805-RES"))
    )
    (comp (ref "R3")
      (value "88.7k")
      (footprint "eagle-import:0805")
      (libsource (lib "eagle-import") (part "SwitcherPowerStage_RESISTOR0805-RES"))
    )
    (comp (ref "R8")
      (value "237k")
      (footprint "eagle-import:0805")
      (libsource (lib "eagle-import") (part "SwitcherPowerStage_RESISTOR0805-RES"))
    )
    (comp (ref "R9")
      (value "7.68k")
      (footprint "eagle-import:0805")
      (libsource (lib "eagle-import") (part "SwitcherPowerStage_RESISTOR0805-RES"))
    )
    (comp (ref "R10")
      (value "59k")
      (footprint "eagle-import:0805")
      (libsource (lib "eagle-import") (part "SwitcherPowerStage_RESISTOR0805-RES"))
    )
    (comp (ref "R11")
      (value "10k")
      (footprint "eagle-import:0805")
      (libsource (lib "eagle-import") (part "SwitcherPowerStage_RESISTOR0805-RES"))
    )
    (comp (ref "U$13")
      (value "SLF12555T")
      (footprint "eagle-import:SLF12555")
      (libsource (lib "eagle-import") (part "SLF12555T"))
    )
    (comp (ref "U$16")
      (value "MINIFITJR4PIN")
      (footprint "eagle-import:0039288040")
      (libsource (lib "eagle-import") (part "MINIFITJR4PIN"))
    )
    (comp (ref "U$18")
      (value "MICROCLASP2")
      (footprint "eagle-import:55932-0210")
      (libsource (lib "eagle-import") (part "MICROCLASP2"))
    )
    (comp (ref "U1")
      (value "TPS73733-Q1_DRB_8")
      (footprint "eagle-import:DRB8_1P75X1P5")
      (fields
        (field (name "GENERIC_PART_NUMBER") "TPS73733-Q1")
        (field (name "MANUFACTURER") "Texas Instruments")
        (field (name "MANUFACTURER_PART_NUMBER") "tps73733-q1_drb_8")
      )
      (libsource (lib "eagle-import") (part "TPS73733-Q1_DRB_8"))
    )
    (comp (ref "U4")
      (value "TPS54240_DRC_10")
      (footprint "eagle-import:DRC10_2P4X1P65")
      (fields
        (field (name "GENERIC_PART_NUMBER") "TPS54240")
        (field (name "MANUFACTURER") "Texas Instruments")
        (field (name "MANUFACTURER_PART_NUMBER") "tps54240_drc_10")
      )
      (libsource (lib "eagle-import") (part "TPS54240_DRC_10"))
    )
    (comp (ref "U5")
      (value "LP38692_NGG_6")
      (footprint "eagle-import:SDE06A")
      (fields (field (name "PARTNUMBER") "LP38692SD-18"))
      (libsource (lib "eagle-import") (part "LP38692_NGG_6"))
    )
  )
  (nets
    (net (code "1") (name "*SCS") (class "Default")
      (node (ref "IC1") (pin "4") (pinfunction "SCS-_4") (pintype "input"))
      (node (ref "TP1") (pin "TP") (pinfunction "TP_TP") (pintype "input"))
      (node (ref "U$1") (pin "52") (pinfunction "RP56/RC8_52") (pintype "passive"))
    )
    (net (code "2") (name "AN4") (class "Default")
      (node (ref "U$1") (pin "17") (pinfunction "PGEC1/AN4/C1IN1+/RPI34/RB2_17") (pintype "passive"))
    )
    (net (code "3") (name "AN5") (class "Default")
      (node (ref "U$1") (pin "18") (pinfunction "PGED1/AN5/C1IN1-/RP35/RB3_18") (pintype "passive"))
    )
    (net (code "4") (name "CANRX") (class "Default")
      (node (ref "U$1") (pin "58") (pinfunction "RPI96/RF0_58") (pintype "passive"))
      (node (ref "U2") (pin "4") (pinfunction "R_4") (pintype "passive"))
    )
    (net (code "5") (name "CANTX") (class "Default")
      (node (ref "U$1") (pin "59") (pinfunction "RP97/RF1_59") (pintype "passive"))
      (node (ref "U2") (pin "1") (pinfunction "D_1") (pintype "passive"))
    )
    (net (code "6") (name "CAN_H") (class "Default")
      (node (ref "R17") (pin "2") (pinfunction "2_2") (pintype "passive"))
      (node (ref "U2") (pin "7") (pinfunction "CANH_7") (pintype "passive"))
    )
    (net (code "7") (name "CAN_L") (class "Default")
      (node (ref "SJ8") (pin "2") (pinfunction "2_2") (pintype "passive"))
      (node (ref "U2") (pin "6") (pinfunction "CANL_6") (pintype "passive"))
    )
    (net (code "8") (name "CRNT1") (class "Default")
      (node (ref "IC1") (pin "21") (pinfunction "SO1_21") (pintype "input"))
      (node (ref "U$1") (pin "13") (pinfunction "AN0/OA2OUT/RA0_13") (pintype "passive"))
    )
    (net (code "9") (name "CRNT2") (class "Default")
      (node (ref "IC1") (pin "22") (pinfunction "SO2_22") (pintype "input"))
      (node (ref "U$1") (pin "14") (pinfunction "AN1/C2IN1+/RA1_14") (pintype "passive"))
    )
    (net (code "10") (name "DC_CAL") (class "Default")
      (node (ref "IC1") (pin "8") (pinfunction "DC_CAL_8") (pintype "passive"))
      (node (ref "U$1") (pin "53") (pinfunction "RD5_53") (pintype "passive"))
    )
    (net (code "11") (name "DRV_GND") (class "Default")
      (node (ref "C16") (pin "2") (pinfunction "2_2") (pintype "passive"))
      (node (ref "C18") (pin "1") (pinfunction "1_1") (pintype "passive"))
      (node (ref "C19") (pin "1") (pinfunction "1_1") (pintype "passive"))
      (node (ref "C3") (pin "2") (pinfunction "2_2") (pintype "passive"))
      (node (ref "C4") (pin "2") (pinfunction "2_2") (pintype "passive"))
      (node (ref "IC1") (pin "24") (pinfunction "AGND_24") (pintype "power_in"))
      (node (ref "IC1") (pin "46") (pinfunction "GND_46") (pintype "power_in"))
      (node (ref "IC1") (pin "47") (pinfunction "GND_47") (pintype "power_in"))
      (node (ref "IC1") (pin "48") (pinfunction "GND_48") (pintype "power_in"))
      (node (ref "IC1") (pin "49") (pinfunction "GND_49") (pintype "power_in"))
      (node (ref "R1") (pin "1") (pinfunction "1_1") (pintype "passive"))
      (node (ref "U10") (pin "1") (pinfunction "P$1_1") (pintype "bidirectional"))
      (node (ref "U9") (pin "2") (pinfunction "P$2_2") (pintype "bidirectional"))
    )
    (net (code "12") (name "EN_A") (class "Default")
      (node (ref "U$1") (pin "36") (pinfunction "SDA1/RPI52/RC4_36") (pintype "passive"))
      (node (ref "U3") (pin "15") (pinfunction "ROUT1_15") (pintype "passive"))
    )
    (net (code "13") (name "EN_A+") (class "Default")
      (node (ref "U3") (pin "2") (pinfunction "RIN1+_2") (pintype "passive"))
    )
    (net (code "14") (name "EN_A-") (class "Default")
      (node (ref "U3") (pin "1") (pinfunction "RIN1_1") (pintype "passive"))
    )
    (net (code "15") (name "EN_B") (class "Default")
      (node (ref "U$1") (pin "35") (pinfunction "SCK1/RPI51/RC3_35") (pintype "passive"))
      (node (ref "U3") (pin "14") (pinfunction "ROUT2_14") (pintype "passive"))
    )
    (net (code "16") (name "EN_B+") (class "Default")
      (node (ref "U3") (pin "3") (pinfunction "RIN2+_3") (pintype "passive"))
    )
    (net (code "17") (name "EN_B-") (class "Default")
      (node (ref "U3") (pin "4") (pinfunction "RIN2_4") (pintype "passive"))
    )
    (net (code "18") (name "EN_C") (class "Default")
      (node (ref "U$1") (pin "34") (pinfunction "SDI1/RPI25/RA9_34") (pintype "passive"))
      (node (ref "U3") (pin "11") (pinfunction "ROUT3_11") (pintype "passive"))
    )
    (net (code "19") (name "EN_C+") (class "Default")
      (node (ref "U3") (pin "6") (pinfunction "RIN3+_6") (pintype "passive"))
    )
    (net (code "20") (name "EN_C-") (class "Default")
      (node (ref "U3") (pin "5") (pinfunction "RIN3_5") (pintype "passive"))
    )
    (net (code "21") (name "EN_GATE") (class "Default")
      (node (ref "IC1") (pin "12") (pinfunction "EN_GATE_12") (pintype "input"))
      (node (ref "U$1") (pin "54") (pinfunction "RD6_54") (pintype "passive"))
    )
    (net (code "22") (name "GH_A") (class "Default")
      (node (ref "IC1") (pin "43") (pinfunction "GH_A_43") (pintype "output"))
      (node (ref "U$3") (pin "4") (pinfunction "G_4") (pintype "passive"))
    )
    (net (code "23") (name "GH_B") (class "Default")
      (node (ref "IC1") (pin "38") (pinfunction "GH_B_38") (pintype "output"))
      (node (ref "U$4") (pin "4") (pinfunction "G_4") (pintype "passive"))
    )
    (net (code "24") (name "GH_C") (class "Default")
      (node (ref "IC1") (pin "33") (pinfunction "GH_C_33") (pintype "output"))
      (node (ref "U$5") (pin "4") (pinfunction "G_4") (pintype "passive"))
    )
    (net (code "25") (name "GL_A") (class "Default")
      (node (ref "IC1") (pin "41") (pinfunction "GL_A_41") (pintype "output"))
      (node (ref "U$6") (pin "4") (pinfunction "G_4") (pintype "passive"))
    )
    (net (code "26") (name "GL_B") (class "Default")
      (node (ref "IC1") (pin "36") (pinfunction "GL_B_36") (pintype "output"))
      (node (ref "U$7") (pin "4") (pinfunction "G_4") (pintype "passive"))
    )
    (net (code "27") (name "GL_C") (class "Default")
      (node (ref "IC1") (pin "31") (pinfunction "GL_C_31") (pintype "output"))
      (node (ref "U$8") (pin "4") (pinfunction "G_4") (pintype "passive"))
    )
    (net (code "28") (name "GND") (class "Default")
      (node (ref "C20") (pin "2") (pinfunction "2_2") (pintype "passive"))
      (node (ref "C21") (pin "2") (pinfunction "2_2") (pintype "passive"))
      (node (ref "C22") (pin "1") (pinfunction "1_1") (pintype "passive"))
      (node (ref "C23") (pin "1") (pinfunction "1_1") (pintype "passive"))
      (node (ref "C24") (pin "2") (pinfunction "2_2") (pintype "passive"))
      (node (ref "C25") (pin "2") (pinfunction "2_2") (pintype "passive"))
      (node (ref "C26") (pin "2") (pinfunction "2_2") (pintype "passive"))
      (node (ref "C7") (pin "2") (pinfunction "2_2") (pintype "passive"))
      (node (ref "JP3") (pin "3") (pinfunction "3_3") (pintype "passive"))
      (node (ref "LED1") (pin "2") (pinfunction "C_2") (pintype "passive"))
      (node (ref "LED2") (pin "2") (pinfunction "C_2") (pintype "passive"))
      (node (ref "LED3") (pin "2") (pinfunction "C_2") (pintype "passive"))
      (node (ref "LED4") (pin "2") (pinfunction "C_2") (pintype "passive"))
      (node (ref "R19") (pin "2") (pinfunction "2_2") (pintype "passive"))
      (node (ref "U$1") (pin "20") (pinfunction "AVSS_20") (pintype "passive"))
      (node (ref "U$1") (pin "25") (pinfunction "VSS_3_25") (pintype "passive"))
      (node (ref "U$1") (pin "41") (pinfunction "VSS_41") (pintype "passive"))
      (node (ref "U$1") (pin "9") (pinfunction "VSS_2_9") (pintype "passive"))
      (node (ref "U2") (pin "2") (pinfunction "GND_2") (pintype "passive"))
      (node (ref "U3") (pin "12") (pinfunction "GND_12") (pintype "passive"))
      (node (ref "U3") (pin "9") (pinfunction "*EN_9") (pintype "passive"))
      (node (ref "U9") (pin "1") (pinfunction "P$1_1") (pintype "bidirectional"))
    )
    (net (code "29") (name "MCLR") (class "Default")
      (node (ref "JP3") (pin "1") (pinfunction "1_1") (pintype "passive"))
      (node (ref "R5") (pin "1") (pinfunction "1_1") (pintype "passive"))
      (node (ref "U$1") (pin "7") (pinfunction "*MCLR_7") (pintype "passive"))
    )
    (net (code "30") (name "MISO") (class "Default")
      (node (ref "IC1") (pin "6") (pinfunction "SDO_6") (pintype "output"))
      (node (ref "TP3") (pin "TP") (pinfunction "TP_TP") (pintype "input"))
      (node (ref "U$1") (pin "50") (pinfunction "RP54/RC6_50") (pintype "passive"))
    )
    (net (code "31") (name "MOSI") (class "Default")
      (node (ref "IC1") (pin "5") (pinfunction "SDI_5") (pintype "input"))
      (node (ref "TP2") (pin "TP") (pinfunction "TP_TP") (pintype "input"))
      (node (ref "U$1") (pin "51") (pinfunction "RP55/RC7_51") (pintype "passive"))
    )
    (net (code "32") (name "Net-(C7-Pad1)") (class "Default")
      (node (ref "C7") (pin "1") (pinfunction "1_1") (pintype "passive"))
      (node (ref "R5") (pin "2") (pinfunction "2_2") (pintype "passive"))
      (node (ref "R6") (pin "2") (pinfunction "2_2") (pintype "passive"))
    )
    (net (code "33") (name "Net-(C14-Pad1)") (class "Default")
      (node (ref "C14") (pin "1") (pinfunction "1_1") (pintype "passive"))
      (node (ref "R9") (pin "1") (pinfunction "1_1") (pintype "passive"))
    )
    (net (code "34") (name "Net-(C28-Pad1)") (class "Default")
      (node (ref "C28") (pin "1") (pinfunction "1_1") (pintype "passive"))
      (node (ref "R20") (pin "1") (pinfunction "1_1") (pintype "passive"))
    )
    (net (code "35") (name "Net-(IC1-AVDD)") (class "Default")
      (node (ref "C19") (pin "2") (pinfunction "2_2") (pintype "passive"))
      (node (ref "IC1") (pin "23") (pinfunction "AVDD_23") (pintype "power_in"))
    )
    (net (code "36") (name "Net-(IC1-BST_A)") (class "Default")
      (node (ref "C9") (pin "1") (pinfunction "1_1") (pintype "passive"))
      (node (ref "IC1") (pin "44") (pinfunction "BST_A_44") (pintype "passive"))
    )
    (net (code "37") (name "Net-(IC1-BST_B)") (class "Default")
      (node (ref "C10") (pin "1") (pinfunction "1_1") (pintype "passive"))
      (node (ref "IC1") (pin "39") (pinfunction "BST_B_39") (pintype "passive"))
    )
    (net (code "38") (name "Net-(IC1-BST_C)") (class "Default")
      (node (ref "C11") (pin "1") (pinfunction "1_1") (pintype "passive"))
      (node (ref "IC1") (pin "34") (pinfunction "BST_C_34") (pintype "passive"))
    )
    (net (code "39") (name "Net-(IC1-CP1)") (class "Default")
      (node (ref "C17") (pin "1") (pinfunction "1_1") (pintype "passive"))
      (node (ref "IC1") (pin "10") (pinfunction "CP1_10") (pintype "bidirectional"))
    )
    (net (code "40") (name "Net-(IC1-CP2)") (class "Default")
      (node (ref "C17") (pin "2") (pinfunction "2_2") (pintype "passive"))
      (node (ref "IC1") (pin "11") (pinfunction "CP2_11") (pintype "bidirectional"))
    )
    (net (code "41") (name "Net-(IC1-DTC)") (class "Default")
      (node (ref "IC1") (pin "3") (pinfunction "DTC_3") (pintype "input"))
      (node (ref "R1") (pin "2") (pinfunction "2_2") (pintype "passive"))
    )
    (net (code "42") (name "Net-(IC1-DVDD)") (class "Default")
      (node (ref "C18") (pin "2") (pinfunction "2_2") (pintype "passive"))
      (node (ref "IC1") (pin "19") (pinfunction "DVDD_19") (pintype "power_in"))
    )
    (net (code "43") (name "Net-(IC1-FAULT-)") (class "Default")
      (node (ref "IC1") (pin "2") (pinfunction "FAULT-_2") (pintype "input"))
      (node (ref "TP7") (pin "TP") (pinfunction "TP_TP") (pintype "input"))
    )
    (net (code "44") (name "Net-(IC1-GVDD)") (class "Default")
      (node (ref "C16") (pin "1") (pinfunction "1_1") (pintype "passive"))
      (node (ref "IC1") (pin "9") (pinfunction "GVDD_9") (pintype "power_in"))
    )
    (net (code "45") (name "Net-(IC1-OCTW-)") (class "Default")
      (node (ref "IC1") (pin "1") (pinfunction "OCTW-_1") (pintype "input"))
      (node (ref "TP6") (pin "TP") (pinfunction "TP_TP") (pintype "input"))
    )
    (net (code "46") (name "Net-(LED1-A)") (class "Default")
      (node (ref "LED1") (pin "1") (pinfunction "A_1") (pintype "passive"))
      (node (ref "RN1") (pin "P$5") (pinfunction "5_P$5") (pintype "passive"))
    )
    (net (code "47") (name "Net-(LED2-A)") (class "Default")
      (node (ref "LED2") (pin "1") (pinfunction "A_1") (pintype "passive"))
      (node (ref "RN1") (pin "P$6") (pinfunction "6_P$6") (pintype "passive"))
    )
    (net (code "48") (name "Net-(LED3-A)") (class "Default")
      (node (ref "LED3") (pin "1") (pinfunction "A_1") (pintype "passive"))
      (node (ref "RN1") (pin "P$7") (pinfunction "7_P$7") (pintype "passive"))
    )
    (net (code "49") (name "Net-(LED4-A)") (class "Default")
      (node (ref "LED4") (pin "1") (pinfunction "A_1") (pintype "passive"))
      (node (ref "RN1") (pin "P$8") (pinfunction "8_P$8") (pintype "passive"))
    )
    (net (code "50") (name "Net-(R17-Pad1)") (class "Default")
      (node (ref "R17") (pin "1") (pinfunction "1_1") (pintype "passive"))
      (node (ref "SJ8") (pin "1") (pinfunction "1_1") (pintype "passive"))
    )
    (net (code "51") (name "Net-(RN1-1)") (class "Default")
      (node (ref "RN1") (pin "P$1") (pinfunction "1_P$1") (pintype "passive"))
      (node (ref "U$1") (pin "48") (pinfunction "TCK/CVREF1O/ASCL1/RP40/T4CK/RB8_48") (pintype "passive"))
    )
    (net (code "52") (name "Net-(RN1-2)") (class "Default")
      (node (ref "RN1") (pin "P$2") (pinfunction "2_P$2") (pintype "passive"))
      (node (ref "U$1") (pin "47") (pinfunction "RC13_47") (pintype "passive"))
    )
    (net (code "53") (name "Net-(RN1-3)") (class "Default")
      (node (ref "RN1") (pin "P$3") (pinfunction "3_P$3") (pintype "passive"))
      (node (ref "U$1") (pin "46") (pinfunction "RP39/INT0/RB7_46") (pintype "passive"))
    )
    (net (code "54") (name "Net-(RN1-4)") (class "Default")
      (node (ref "RN1") (pin "P$4") (pinfunction "4_P$4") (pintype "passive"))
      (node (ref "U$1") (pin "45") (pinfunction "RPI58/RC10_45") (pintype "passive"))
    )
    (net (code "55") (name "Net-(U$1-PGED3{slash}VREF-{slash}AN2{slash}C2IN1-{slash}*SS1{slash}RPI32{slash}CTED2{slash}RB0)") (class "Default")
      (node (ref "R18") (pin "2") (pinfunction "2_2") (pintype "passive"))
      (node (ref "R19") (pin "1") (pinfunction "1_1") (pintype "passive"))
      (node (ref "U$1") (pin "15") (pinfunction "PGED3/VREF-/AN2/C2IN1-/*SS1/RPI32/CTED2/RB0_15") (pintype "passive"))
    )
    (net (code "56") (name "Net-(U$1-RP118{slash}RG6)") (class "Default")
      (node (ref "SJ4") (pin "2") (pinfunction "2_2") (pintype "passive"))
      (node (ref "U$1") (pin "4") (pinfunction "RP118/RG6_4") (pintype "passive"))
    )
    (net (code "57") (name "Net-(U$1-RP120{slash}RG8)") (class "Default")
      (node (ref "SJ6") (pin "2") (pinfunction "2_2") (pintype "passive"))
      (node (ref "U$1") (pin "6") (pinfunction "RP120/RG8_6") (pintype "passive"))
    )
    (net (code "58") (name "Net-(U$1-RPI119{slash}RG7)") (class "Default")
      (node (ref "SJ5") (pin "2") (pinfunction "2_2") (pintype "passive"))
      (node (ref "U$1") (pin "5") (pinfunction "RPI119/RG7_5") (pintype "passive"))
    )
    (net (code "59") (name "Net-(U$1-RPI121{slash}RG9)") (class "Default")
      (node (ref "SJ7") (pin "2") (pinfunction "2_2") (pintype "passive"))
      (node (ref "U$1") (pin "8") (pinfunction "RPI121/RG9_8") (pintype "passive"))
    )
    (net (code "60") (name "Net-(U$1-TDI{slash}RA7)") (class "Default")
      (node (ref "SJ1") (pin "2") (pinfunction "2_2") (pintype "passive"))
      (node (ref "U$1") (pin "1") (pinfunction "TDI/RA7_1") (pintype "passive"))
    )
    (net (code "61") (name "Net-(U$1-VCAP)") (class "Default")
      (node (ref "C20") (pin "1") (pinfunction "1_1") (pintype "passive"))
      (node (ref "U$1") (pin "56") (pinfunction "VCAP_56") (pintype "passive"))
    )
    (net (code "62") (name "Net-(U$13-1)") (class "Default")
      (node (ref "C8") (pin "2") (pinfunction "2_2") (pintype "passive"))
      (node (ref "D1") (pin "C") (pinfunction "C_C") (pintype "passive"))
      (node (ref "U$13") (pin "P$1") (pinfunction "1_P$1") (pintype "passive"))
      (node (ref "U4") (pin "10") (pinfunction "PH_10") (pintype "input"))
    )
    (net (code "63") (name "Net-(U4-BOOT)") (class "Default")
      (node (ref "C8") (pin "1") (pinfunction "1_1") (pintype "passive"))
      (node (ref "U4") (pin "1") (pinfunction "BOOT_1") (pintype "output"))
    )
    (net (code "64") (name "Net-(U4-COMP)") (class "Default")
      (node (ref "C15") (pin "1") (pinfunction "1_1") (pintype "passive"))
      (node (ref "R9") (pin "2") (pinfunction "2_2") (pintype "passive"))
      (node (ref "U4") (pin "8") (pinfunction "COMP_8") (pintype "output"))
    )
    (net (code "65") (name "Net-(U4-EN)") (class "Default")
      (node (ref "R2") (pin "1") (pinfunction "1_1") (pintype "passive"))
      (node (ref "R3") (pin "2") (pinfunction "2_2") (pintype "passive"))
      (node (ref "U4") (pin "3") (pinfunction "EN_3") (pintype "input"))
    )
    (net (code "66") (name "Net-(U4-RT{slash}CLK)") (class "Default")
      (node (ref "R8") (pin "2") (pinfunction "2_2") (pintype "passive"))
      (node (ref "U4") (pin "5") (pinfunction "RT/CLK_5") (pintype "input"))
    )
    (net (code "67") (name "Net-(U4-SS{slash}TR)") (class "Default")
      (node (ref "C6") (pin "1") (pinfunction "1_1") (pintype "passive"))
      (node (ref "U4") (pin "4") (pinfunction "SS/TR_4") (pintype "input"))
    )
    (net (code "68") (name "Net-(U4-VSENSE)") (class "Default")
      (node (ref "R10") (pin "1") (pinfunction "1_1") (pintype "passive"))
      (node (ref "R11") (pin "2") (pinfunction "2_2") (pintype "passive"))
      (node (ref "U4") (pin "7") (pinfunction "VSENSE_7") (pintype "input"))
    )
    (net (code "69") (name "PGC") (class "Default")
      (node (ref "JP3") (pin "5") (pinfunction "5_5") (pintype "passive"))
      (node (ref "U$1") (pin "44") (pinfunction "PGEC2/ASCL2/RP38/RB6_44") (pintype "passive"))
    )
    (net (code "70") (name "PGD") (class "Default")
      (node (ref "JP3") (pin "4") (pinfunction "4_4") (pintype "passive"))
      (node (ref "U$1") (pin "43") (pinfunction "PGED2/ASDA2/RP37/RB5_43") (pintype "passive"))
    )
    (net (code "71") (name "PGND") (class "Default")
      (node (ref "C12") (pin "2") (pinfunction "2_2") (pintype "passive"))
      (node (ref "C13") (pin "2") (pinfunction "2_2") (pintype "passive"))
      (node (ref "C14") (pin "2") (pinfunction "2_2") (pintype "passive"))
      (node (ref "C15") (pin "2") (pinfunction "2_2") (pintype "passive"))
      (node (ref "C27") (pin "2") (pinfunction "-_2") (pintype "passive"))
      (node (ref "C28") (pin "2") (pinfunction "2_2") (pintype "passive"))
      (node (ref "C29") (pin "2") (pinfunction "2_2") (pintype "passive"))
      (node (ref "C30") (pin "2") (pinfunction "2_2") (pintype "passive"))
      (node (ref "C31") (pin "2") (pinfunction "2_2") (pintype "passive"))
      (node (ref "C32") (pin "2") (pinfunction "2_2") (pintype "passive"))
      (node (ref "C5") (pin "2") (pinfunction "2_2") (pintype "passive"))
      (node (ref "C6") (pin "2") (pinfunction "2_2") (pintype "passive"))
      (node (ref "D1") (pin "A") (pinfunction "A_A") (pintype "passive"))
      (node (ref "R11") (pin "1") (pinfunction "1_1") (pintype "passive"))
      (node (ref "R3") (pin "1") (pinfunction "1_1") (pintype "passive"))
      (node (ref "R4") (pin "1") (pinfunction "1_1") (pintype "passive"))
      (node (ref "R7") (pin "1") (pinfunction "1_1") (pintype "passive"))
      (node (ref "R8") (pin "1") (pinfunction "1_1") (pintype "passive"))
      (node (ref "U$10") (pin "P$2") (pinfunction "P$2_P$2") (pintype "bidirectional"))
      (node (ref "U$11") (pin "P$2") (pinfunction "P$2_P$2") (pintype "bidirectional"))
      (node (ref "U$2") (pin "P$2") (pinfunction "P$2_P$2") (pintype "bidirectional"))
      (node (ref "U$7") (pin "1") (pinfunction "S_1") (pintype "passive"))
      (node (ref "U$7") (pin "2") (pinfunction "S_2") (pintype "passive"))
      (node (ref "U$7") (pin "3") (pinfunction "S_3") (pintype "passive"))
      (node (ref "U1") (pin "4") (pinfunction "GND_4") (pintype "power_in"))
      (node (ref "U1") (pin "9") (pinfunction "EPAD_9") (pintype "passive"))
      (node (ref "U1") (pin "P$1") (pinfunction "EPAD_P$1") (pintype "passive"))
      (node (ref "U1") (pin "P$2") (pinfunction "EPAD_P$2") (pintype "passive"))
      (node (ref "U1") (pin "P$3") (pinfunction "EPAD_P$3") (pintype "passive"))
      (node (ref "U1") (pin "P$4") (pinfunction "EPAD_P$4") (pintype "passive"))
      (node (ref "U10") (pin "2") (pinfunction "P$2_2") (pintype "bidirectional"))
      (node (ref "U4") (pin "9") (pinfunction "GND_9") (pintype "power_in"))
      (node (ref "U5") (pin "2") (pinfunction "GND_2") (pintype "passive"))
      (node (ref "U5") (pin "7") (pinfunction "7_7") (pintype "passive"))
    )
    (net (code "72") (name "PVDD") (class "Default")
      (node (ref "C27") (pin "1") (pinfunction "+_1") (pintype "passive"))
      (node (ref "C3") (pin "1") (pinfunction "1_1") (pintype "passive"))
      (node (ref "C4") (pin "1") (pinfunction "1_1") (pintype "passive"))
      (node (ref "C5") (pin "1") (pinfunction "1_1") (pintype "passive"))
      (node (ref "IC1") (pin "25") (pinfunction "PVDD_25") (pintype "power_in"))
      (node (ref "R18") (pin "1") (pinfunction "1_1") (pintype "passive"))
      (node (ref "R2") (pin "2") (pinfunction "2_2") (pintype "passive"))
      (node (ref "R20") (pin "2") (pinfunction "2_2") (pintype "passive"))
      (node (ref "U$3") (pin "5") (pinfunction "D_5") (pintype "passive"))
      (node (ref "U$3") (pin "P$1") (pinfunction "D_P$1") (pintype "passive"))
      (node (ref "U$3") (pin "P$2") (pinfunction "D_P$2") (pintype "passive"))
      (node (ref "U$3") (pin "P$3") (pinfunction "D_P$3") (pintype "passive"))
      (node (ref "U$3") (pin "P$4") (pinfunction "D_P$4") (pintype "passive"))
      (node (ref "U$3") (pin "P$5") (pinfunction "D_P$5") (pintype "passive"))
      (node (ref "U$3") (pin "P$6") (pinfunction "D_P$6") (pintype "passive"))
      (node (ref "U$3") (pin "P$7") (pinfunction "D_P$7") (pintype "passive"))
      (node (ref "U$3") (pin "P$8") (pinfunction "D_P$8") (pintype "passive"))
      (node (ref "U$3") (pin "P$9") (pinfunction "D_P$9") (pintype "passive"))
      (node (ref "U$4") (pin "5") (pinfunction "D_5") (pintype "passive"))
      (node (ref "U$4") (pin "P$1") (pinfunction "D_P$1") (pintype "passive"))
      (node (ref "U$4") (pin "P$2") (pinfunction "D_P$2") (pintype "passive"))
      (node (ref "U$4") (pin "P$3") (pinfunction "D_P$3") (pintype "passive"))
      (node (ref "U$4") (pin "P$4") (pinfunction "D_P$4") (pintype "passive"))
      (node (ref "U$4") (pin "P$5") (pinfunction "D_P$5") (pintype "passive"))
      (node (ref "U$4") (pin "P$6") (pinfunction "D_P$6") (pintype "passive"))
      (node (ref "U$4") (pin "P$7") (pinfunction "D_P$7") (pintype "passive"))
      (node (ref "U$4") (pin "P$8") (pinfunction "D_P$8") (pintype "passive"))
      (node (ref "U$4") (pin "P$9") (pinfunction "D_P$9") (pintype "passive"))
      (node (ref "U$5") (pin "5") (pinfunction "D_5") (pintype "passive"))
      (node (ref "U$5") (pin "P$1") (pinfunction "D_P$1") (pintype "passive"))
      (node (ref "U$5") (pin "P$2") (pinfunction "D_P$2") (pintype "passive"))
      (node (ref "U$5") (pin "P$3") (pinfunction "D_P$3") (pintype "passive"))
      (node (ref "U$5") (pin "P$4") (pinfunction "D_P$4") (pintype "passive"))
      (node (ref "U$5") (pin "P$5") (pinfunction "D_P$5") (pintype "passive"))
      (node (ref "U$5") (pin "P$6") (pinfunction "D_P$6") (pintype "passive"))
      (node (ref "U$5") (pin "P$7") (pinfunction "D_P$7") (pintype "passive"))
      (node (ref "U$5") (pin "P$8") (pinfunction "D_P$8") (pintype "passive"))
      (node (ref "U$5") (pin "P$9") (pinfunction "D_P$9") (pintype "passive"))
      (node (ref "U4") (pin "2") (pinfunction "VIN_2") (pintype "input"))
    )
    (net (code "73") (name "PWM1H") (class "Default")
      (node (ref "IC1") (pin "13") (pinfunction "INH_A_13") (pintype "input"))
      (node (ref "U$1") (pin "2") (pinfunction "RPI46/PWM1H/T3CK/RB14_2") (pintype "passive"))
    )
    (net (code "74") (name "PWM1L") (class "Default")
      (node (ref "IC1") (pin "14") (pinfunction "INL_A_14") (pintype "input"))
      (node (ref "U$1") (pin "3") (pinfunction "RPI47/PWM1L/T5CK/RB15_3") (pintype "passive"))
    )
    (net (code "75") (name "PWM2H") (class "Default")
      (node (ref "IC1") (pin "15") (pinfunction "INH_B_15") (pintype "input"))
      (node (ref "U$1") (pin "62") (pinfunction "RPI44/PWM2H/RB12_62") (pintype "passive"))
    )
    (net (code "76") (name "PWM2L") (class "Default")
      (node (ref "IC1") (pin "16") (pinfunction "INL_B_16") (pintype "input"))
      (node (ref "U$1") (pin "63") (pinfunction "RPI45/PWM2L/CTPLS/RB13_63") (pintype "passive"))
    )
    (net (code "77") (name "PWM3H") (class "Default")
      (node (ref "IC1") (pin "17") (pinfunction "INH_C_17") (pintype "input"))
      (node (ref "U$1") (pin "60") (pinfunction "RP42/PWM3H/RB10_60") (pintype "passive"))
    )
    (net (code "78") (name "PWM3L") (class "Default")
      (node (ref "IC1") (pin "18") (pinfunction "INL_C_18") (pintype "input"))
      (node (ref "U$1") (pin "61") (pinfunction "RB43/PWM3L/RB11_61") (pintype "passive"))
    )
    (net (code "79") (name "RA11") (class "Default")
      (node (ref "U$1") (pin "12") (pinfunction "AN9/RPI27/RA11_12") (pintype "passive"))
    )
    (net (code "80") (name "RA12") (class "Default")
      (node (ref "U$1") (pin "11") (pinfunction "AN10/RPI28/RA12_11") (pintype "passive"))
    )
    (net (code "81") (name "SCLK") (class "Default")
      (node (ref "IC1") (pin "7") (pinfunction "SCLK_7") (pintype "input"))
      (node (ref "TP4") (pin "TP") (pinfunction "TP_TP") (pintype "input"))
      (node (ref "U$1") (pin "49") (pinfunction "TMS/ASDA1/RP41/RB9_49") (pintype "passive"))
    )
    (net (code "82") (name "SH_A") (class "Default")
      (node (ref "C9") (pin "2") (pinfunction "2_2") (pintype "passive"))
      (node (ref "IC1") (pin "42") (pinfunction "SH_A_42") (pintype "passive"))
      (node (ref "U$3") (pin "1") (pinfunction "S_1") (pintype "passive"))
      (node (ref "U$3") (pin "2") (pinfunction "S_2") (pintype "passive"))
      (node (ref "U$3") (pin "3") (pinfunction "S_3") (pintype "passive"))
      (node (ref "U$6") (pin "5") (pinfunction "D_5") (pintype "passive"))
      (node (ref "U$6") (pin "P$1") (pinfunction "D_P$1") (pintype "passive"))
      (node (ref "U$6") (pin "P$2") (pinfunction "D_P$2") (pintype "passive"))
      (node (ref "U$6") (pin "P$3") (pinfunction "D_P$3") (pintype "passive"))
      (node (ref "U$6") (pin "P$4") (pinfunction "D_P$4") (pintype "passive"))
      (node (ref "U$6") (pin "P$5") (pinfunction "D_P$5") (pintype "passive"))
      (node (ref "U$6") (pin "P$6") (pinfunction "D_P$6") (pintype "passive"))
      (node (ref "U$6") (pin "P$7") (pinfunction "D_P$7") (pintype "passive"))
      (node (ref "U$6") (pin "P$8") (pinfunction "D_P$8") (pintype "passive"))
      (node (ref "U$6") (pin "P$9") (pinfunction "D_P$9") (pintype "passive"))
    )
    (net (code "83") (name "SH_B") (class "Default")
      (node (ref "C10") (pin "2") (pinfunction "2_2") (pintype "passive"))
      (node (ref "IC1") (pin "37") (pinfunction "SH_B_37") (pintype "passive"))
      (node (ref "U$4") (pin "1") (pinfunction "S_1") (pintype "passive"))
      (node (ref "U$4") (pin "2") (pinfunction "S_2") (pintype "passive"))
      (node (ref "U$4") (pin "3") (pinfunction "S_3") (pintype "passive"))
      (node (ref "U$7") (pin "5") (pinfunction "D_5") (pintype "passive"))
      (node (ref "U$7") (pin "P$1") (pinfunction "D_P$1") (pintype "passive"))
      (node (ref "U$7") (pin "P$2") (pinfunction "D_P$2") (pintype "passive"))
      (node (ref "U$7") (pin "P$3") (pinfunction "D_P$3") (pintype "passive"))
      (node (ref "U$7") (pin "P$4") (pinfunction "D_P$4") (pintype "passive"))
      (node (ref "U$7") (pin "P$5") (pinfunction "D_P$5") (pintype "passive"))
      (node (ref "U$7") (pin "P$6") (pinfunction "D_P$6") (pintype "passive"))
      (node (ref "U$7") (pin "P$7") (pinfunction "D_P$7") (pintype "passive"))
      (node (ref "U$7") (pin "P$8") (pinfunction "D_P$8") (pintype "passive"))
      (node (ref "U$7") (pin "P$9") (pinfunction "D_P$9") (pintype "passive"))
    )
    (net (code "84") (name "SH_C") (class "Default")
      (node (ref "C11") (pin "2") (pinfunction "2_2") (pintype "passive"))
      (node (ref "IC1") (pin "32") (pinfunction "SH_C_32") (pintype "passive"))
      (node (ref "U$5") (pin "1") (pinfunction "S_1") (pintype "passive"))
      (node (ref "U$5") (pin "2") (pinfunction "S_2") (pintype "passive"))
      (node (ref "U$5") (pin "3") (pinfunction "S_3") (pintype "passive"))
      (node (ref "U$8") (pin "5") (pinfunction "D_5") (pintype "passive"))
      (node (ref "U$8") (pin "P$1") (pinfunction "D_P$1") (pintype "passive"))
      (node (ref "U$8") (pin "P$2") (pinfunction "D_P$2") (pintype "passive"))
      (node (ref "U$8") (pin "P$3") (pinfunction "D_P$3") (pintype "passive"))
      (node (ref "U$8") (pin "P$4") (pinfunction "D_P$4") (pintype "passive"))
      (node (ref "U$8") (pin "P$5") (pinfunction "D_P$5") (pintype "passive"))
      (node (ref "U$8") (pin "P$6") (pinfunction "D_P$6") (pintype "passive"))
      (node (ref "U$8") (pin "P$7") (pinfunction "D_P$7") (pintype "passive"))
      (node (ref "U$8") (pin "P$8") (pinfunction "D_P$8") (pintype "passive"))
      (node (ref "U$8") (pin "P$9") (pinfunction "D_P$9") (pintype "passive"))
    )
    (net (code "85") (name "SL_A") (class "Default")
      (node (ref "IC1") (pin "40") (pinfunction "SL_A_40") (pintype "passive"))
      (node (ref "U$9") (pin "P$2") (pinfunction "P$2_P$2") (pintype "bidirectional"))
    )
    (net (code "86") (name "SL_B") (class "Default")
      (node (ref "IC1") (pin "35") (pinfunction "SL_B_35") (pintype "passive"))
      (node (ref "U$10") (pin "P$1") (pinfunction "P$1_P$1") (pintype "bidirectional"))
    )
    (net (code "87") (name "SL_C") (class "Default")
      (node (ref "IC1") (pin "30") (pinfunction "SL_C_30") (pintype "passive"))
      (node (ref "U$12") (pin "P$2") (pinfunction "P$2_P$2") (pintype "bidirectional"))
    )
    (net (code "88") (name "SN1") (class "Default")
      (node (ref "C12") (pin "1") (pinfunction "1_1") (pintype "passive"))
      (node (ref "IC1") (pin "29") (pinfunction "SN1_29") (pintype "passive"))
      (node (ref "R7") (pin "2") (pinfunction "2_2") (pintype "passive"))
      (node (ref "U$6") (pin "1") (pinfunction "S_1") (pintype "passive"))
      (node (ref "U$6") (pin "2") (pinfunction "S_2") (pintype "passive"))
      (node (ref "U$6") (pin "3") (pinfunction "S_3") (pintype "passive"))
      (node (ref "U$9") (pin "P$1") (pinfunction "P$1_P$1") (pintype "bidirectional"))
    )
    (net (code "89") (name "SN2") (class "Default")
      (node (ref "C13") (pin "1") (pinfunction "1_1") (pintype "passive"))
      (node (ref "IC1") (pin "27") (pinfunction "SN2_27") (pintype "passive"))
      (node (ref "R4") (pin "2") (pinfunction "2_2") (pintype "passive"))
      (node (ref "U$12") (pin "P$1") (pinfunction "P$1_P$1") (pintype "bidirectional"))
      (node (ref "U$8") (pin "1") (pinfunction "S_1") (pintype "passive"))
      (node (ref "U$8") (pin "2") (pinfunction "S_2") (pintype "passive"))
      (node (ref "U$8") (pin "3") (pinfunction "S_3") (pintype "passive"))
    )
    (net (code "90") (name "SP1") (class "Default")
      (node (ref "IC1") (pin "28") (pinfunction "SP1_28") (pintype "passive"))
      (node (ref "U$2") (pin "P$1") (pinfunction "P$1_P$1") (pintype "bidirectional"))
    )
    (net (code "91") (name "SP2") (class "Default")
      (node (ref "IC1") (pin "26") (pinfunction "SP2_26") (pintype "passive"))
      (node (ref "U$11") (pin "P$1") (pinfunction "P$1_P$1") (pintype "bidirectional"))
    )
    (net (code "92") (name "VCC3V3") (class "Default")
      (node (ref "C21") (pin "1") (pinfunction "1_1") (pintype "passive"))
      (node (ref "C22") (pin "2") (pinfunction "2_2") (pintype "passive"))
      (node (ref "C23") (pin "2") (pinfunction "2_2") (pintype "passive"))
      (node (ref "C24") (pin "1") (pinfunction "1_1") (pintype "passive"))
      (node (ref "C25") (pin "1") (pinfunction "1_1") (pintype "passive"))
      (node (ref "C26") (pin "1") (pinfunction "1_1") (pintype "passive"))
      (node (ref "C32") (pin "1") (pinfunction "1_1") (pintype "passive"))
      (node (ref "IC1") (pin "20") (pinfunction "REF_20") (pintype "passive"))
      (node (ref "IC1") (pin "45") (pinfunction "VDD_SPI_45") (pintype "power_in"))
      (node (ref "JP3") (pin "2") (pinfunction "2_2") (pintype "passive"))
      (node (ref "R6") (pin "1") (pinfunction "1_1") (pintype "passive"))
      (node (ref "SJ1") (pin "1") (pinfunction "1_1") (pintype "passive"))
      (node (ref "SJ4") (pin "1") (pinfunction "1_1") (pintype "passive"))
      (node (ref "SJ5") (pin "1") (pinfunction "1_1") (pintype "passive"))
      (node (ref "SJ6") (pin "1") (pinfunction "1_1") (pintype "passive"))
      (node (ref "SJ7") (pin "1") (pinfunction "1_1") (pintype "passive"))
      (node (ref "U$1") (pin "10") (pinfunction "VDD_2_10") (pintype "passive"))
      (node (ref "U$1") (pin "19") (pinfunction "AVDD_19") (pintype "passive"))
      (node (ref "U$1") (pin "26") (pinfunction "VDD_3_26") (pintype "passive"))
      (node (ref "U$1") (pin "38") (pinfunction "VDD_4_38") (pintype "passive"))
      (node (ref "U$1") (pin "57") (pinfunction "VDD_57") (pintype "passive"))
      (node (ref "U1") (pin "1") (pinfunction "OUT_1") (pintype "output"))
      (node (ref "U2") (pin "3") (pinfunction "VCC_3") (pintype "passive"))
      (node (ref "U3") (pin "13") (pinfunction "VCC_13") (pintype "passive"))
      (node (ref "U3") (pin "16") (pinfunction "EN_16") (pintype "passive"))
    )
    (net (code "93") (name "VCC5V0") (class "Default")
      (node (ref "C31") (pin "1") (pinfunction "1_1") (pintype "passive"))
      (node (ref "U1") (pin "5") (pinfunction "EN_5") (pintype "passive"))
      (node (ref "U1") (pin "8") (pinfunction "IN_8") (pintype "input"))
      (node (ref "U5") (pin "4") (pinfunction "VOUT_4") (pintype "output"))
      (node (ref "U5") (pin "5") (pinfunction "SNS_5") (pintype "passive"))
    )
    (net (code "94") (name "VCC5V5") (class "Default")
      (node (ref "C29") (pin "1") (pinfunction "1_1") (pintype "passive"))
      (node (ref "C30") (pin "1") (pinfunction "1_1") (pintype "passive"))
      (node (ref "R10") (pin "2") (pinfunction "2_2") (pintype "passive"))
      (node (ref "U$13") (pin "P$2") (pinfunction "2_P$2") (pintype "passive"))
      (node (ref "U5") (pin "1") (pinfunction "VIN_2_1") (pintype "input"))
      (node (ref "U5") (pin "3") (pinfunction "VEN_3") (pintype "passive"))
      (node (ref "U5") (pin "6") (pinfunction "VIN_6") (pintype "input"))
    )
    (net (code "95") (name "unconnected-(JP3-Pad6)") (class "Default")
      (node (ref "JP3") (pin "6") (pinfunction "6_6") (pintype "passive"))
    )
    (net (code "96") (name "unconnected-(U$1-AN6{slash}OA3OUT{slash}C4IN1+{slash}OCFB{slash}RC0-Pad21)") (class "Default")
      (node (ref "U$1") (pin "21") (pinfunction "AN6/OA3OUT/C4IN1+/OCFB/RC0_21") (pintype "passive"))
    )
    (net (code "97") (name "unconnected-(U$1-AN7{slash}C3IN1-{slash}C4IN1-{slash}RC1-Pad22)") (class "Default")
      (node (ref "U$1") (pin "22") (pinfunction "AN7/C3IN1-/C4IN1-/RC1_22") (pintype "passive"))
    )
    (net (code "98") (name "unconnected-(U$1-AN8{slash}C3IN1+{slash}*U1RTS{slash}BCLK1{slash}FLT3{slash}RC2-Pad23)") (class "Default")
      (node (ref "U$1") (pin "23") (pinfunction "AN8/C3IN1+/*U1RTS/BCLK1/FLT3/RC2_23") (pintype "passive"))
    )
    (net (code "99") (name "unconnected-(U$1-AN11{slash}C1IN2-{slash}*U1CTS{slash}FLT4{slash}RC11-Pad24)") (class "Default")
      (node (ref "U$1") (pin "24") (pinfunction "AN11/C1IN2-/*U1CTS/FLT4/RC11_24") (pintype "passive"))
    )
    (net (code "100") (name "unconnected-(U$1-AN12{slash}C2IN2-{slash}*U2RTS{slash}BCLK2{slash}RE12-Pad27)") (class "Default")
      (node (ref "U$1") (pin "27") (pinfunction "AN12/C2IN2-/*U2RTS/BCLK2/RE12_27") (pintype "passive"))
    )
    (net (code "101") (name "unconnected-(U$1-AN13{slash}C3IN2-{slash}*U2CTS{slash}RE13-Pad28)") (class "Default")
      (node (ref "U$1") (pin "28") (pinfunction "AN13/C3IN2-/*U2CTS/RE13_28") (pintype "passive"))
    )
    (net (code "102") (name "unconnected-(U$1-AN14{slash}RPI94{slash}RE14-Pad29)") (class "Default")
      (node (ref "U$1") (pin "29") (pinfunction "AN14/RPI94/RE14_29") (pintype "passive"))
    )
    (net (code "103") (name "unconnected-(U$1-AN15{slash}RPI95{slash}RE15-Pad30)") (class "Default")
      (node (ref "U$1") (pin "30") (pinfunction "AN15/RPI95/RE15_30") (pintype "passive"))
    )
    (net (code "104") (name "unconnected-(U$1-CVREF2O{slash}SDO1{slash}RP20{slash}T1CK{slash}RA4-Pad33)") (class "Default")
      (node (ref "U$1") (pin "33") (pinfunction "CVREF2O/SDO1/RP20/T1CK/RA4_33") (pintype "passive"))
    )
    (net (code "105") (name "unconnected-(U$1-FLT32{slash}SCL2{slash}RP36{slash}RB4-Pad32)") (class "Default")
      (node (ref "U$1") (pin "32") (pinfunction "FLT32/SCL2/RP36/RB4_32") (pintype "passive"))
    )
    (net (code "106") (name "unconnected-(U$1-OSC1{slash}CLKI{slash}RC12-Pad39)") (class "Default")
      (node (ref "U$1") (pin "39") (pinfunction "OSC1/CLKI/RC12_39") (pintype "passive"))
    )
    (net (code "107") (name "unconnected-(U$1-OSC2{slash}CLKO{slash}RC15-Pad40)") (class "Default")
      (node (ref "U$1") (pin "40") (pinfunction "OSC2/CLKO/RC15_40") (pintype "passive"))
    )
    (net (code "108") (name "unconnected-(U$1-PGEC3{slash}VREF+{slash}AN3{slash}OA1OUT{slash}RPI33{slash}CTED1{slash}RB1-Pad16)") (class "Default")
      (node (ref "U$1") (pin "16") (pinfunction "PGEC3/VREF+/AN3/OA1OUT/RPI33/CTED1/RB1_16") (pintype "passive"))
    )
    (net (code "109") (name "unconnected-(U$1-RD8-Pad42)") (class "Default")
      (node (ref "U$1") (pin "42") (pinfunction "RD8_42") (pintype "passive"))
    )
    (net (code "110") (name "unconnected-(U$1-RP57{slash}RC9-Pad55)") (class "Default")
      (node (ref "U$1") (pin "55") (pinfunction "RP57/RC9_55") (pintype "passive"))
    )
    (net (code "111") (name "unconnected-(U$1-SCL1{slash}RPI53{slash}RC5-Pad37)") (class "Default")
      (node (ref "U$1") (pin "37") (pinfunction "SCL1/RPI53/RC5_37") (pintype "passive"))
    )
    (net (code "112") (name "unconnected-(U$1-SDA2{slash}RPI24{slash}RA8-Pad31)") (class "Default")
      (node (ref "U$1") (pin "31") (pinfunction "SDA2/RPI24/RA8_31") (pintype "passive"))
    )
    (net (code "113") (name "unconnected-(U$1-TDO{slash}RA10-Pad64)") (class "Default")
      (node (ref "U$1") (pin "64") (pinfunction "TDO/RA10_64") (pintype "passive"))
    )
    (net (code "114") (name "unconnected-(U$14-1-PadP$1)") (class "Default")
      (node (ref "U$14") (pin "P$1") (pinfunction "1_P$1") (pintype "bidirectional"))
    )
    (net (code "115") (name "unconnected-(U$14-2-PadP$2)") (class "Default")
      (node (ref "U$14") (pin "P$2") (pinfunction "2_P$2") (pintype "bidirectional"))
    )
    (net (code "116") (name "unconnected-(U$14-3-PadP$3)") (class "Default")
      (node (ref "U$14") (pin "P$3") (pinfunction "3_P$3") (pintype "bidirectional"))
    )
    (net (code "117") (name "unconnected-(U$15-Pad1)") (class "Default")
      (node (ref "U$15") (pin "1") (pinfunction "1_1") (pintype "bidirectional"))
    )
    (net (code "118") (name "unconnected-(U$15-Pad2)") (class "Default")
      (node (ref "U$15") (pin "2") (pinfunction "2_2") (pintype "bidirectional"))
    )
    (net (code "119") (name "unconnected-(U$15-Pad3)") (class "Default")
      (node (ref "U$15") (pin "3") (pinfunction "3_3") (pintype "bidirectional"))
    )
    (net (code "120") (name "unconnected-(U$15-Pad4)") (class "Default")
      (node (ref "U$15") (pin "4") (pinfunction "4_4") (pintype "bidirectional"))
    )
    (net (code "121") (name "unconnected-(U$15-Pad5)") (class "Default")
      (node (ref "U$15") (pin "5") (pinfunction "5_5") (pintype "bidirectional"))
    )
    (net (code "122") (name "unconnected-(U$15-Pad6)") (class "Default")
      (node (ref "U$15") (pin "6") (pinfunction "6_6") (pintype "bidirectional"))
    )
    (net (code "123") (name "unconnected-(U$15-Pad7)") (class "Default")
      (node (ref "U$15") (pin "7") (pinfunction "7_7") (pintype "bidirectional"))
    )
    (net (code "124") (name "unconnected-(U$15-Pad8)") (class "Default")
      (node (ref "U$15") (pin "8") (pinfunction "8_8") (pintype "bidirectional"))
    )
    (net (code "125") (name "unconnected-(U$15-Pad9)") (class "Default")
      (node (ref "U$15") (pin "9") (pinfunction "9_9") (pintype "bidirectional"))
    )
    (net (code "126") (name "unconnected-(U$15-Pad10)") (class "Default")
      (node (ref "U$15") (pin "10") (pinfunction "10_10") (pintype "bidirectional"))
    )
    (net (code "127") (name "unconnected-(U$16-Pad1)") (class "Default")
      (node (ref "U$16") (pin "1") (pinfunction "1_1") (pintype "bidirectional"))
    )
    (net (code "128") (name "unconnected-(U$16-Pad2)") (class "Default")
      (node (ref "U$16") (pin "2") (pinfunction "2_2") (pintype "bidirectional"))
    )
    (net (code "129") (name "unconnected-(U$16-Pad3)") (class "Default")
      (node (ref "U$16") (pin "3") (pinfunction "3_3") (pintype "bidirectional"))
    )
    (net (code "130") (name "unconnected-(U$16-Pad4)") (class "Default")
      (node (ref "U$16") (pin "4") (pinfunction "4_4") (pintype "bidirectional"))
    )
    (net (code "131") (name "unconnected-(U$17-Pad1)") (class "Default")
      (node (ref "U$17") (pin "1") (pinfunction "1_1") (pintype "bidirectional"))
    )
    (net (code "132") (name "unconnected-(U$17-Pad2)") (class "Default")
      (node (ref "U$17") (pin "2") (pinfunction "2_2") (pintype "bidirectional"))
    )
    (net (code "133") (name "unconnected-(U$17-Pad3)") (class "Default")
      (node (ref "U$17") (pin "3") (pinfunction "3_3") (pintype "bidirectional"))
    )
    (net (code "134") (name "unconnected-(U$17-Pad4)") (class "Default")
      (node (ref "U$17") (pin "4") (pinfunction "4_4") (pintype "bidirectional"))
    )
    (net (code "135") (name "unconnected-(U$17-Pad5)") (class "Default")
      (node (ref "U$17") (pin "5") (pinfunction "5_5") (pintype "bidirectional"))
    )
    (net (code "136") (name "unconnected-(U$17-Pad6)") (class "Default")
      (node (ref "U$17") (pin "6") (pinfunction "6_6") (pintype "bidirectional"))
    )
    (net (code "137") (name "unconnected-(U$18-Pad1)") (class "Default")
      (node (ref "U$18") (pin "1") (pinfunction "1_1") (pintype "bidirectional"))
    )
    (net (code "138") (name "unconnected-(U$18-Pad2)") (class "Default")
      (node (ref "U$18") (pin "2") (pinfunction "2_2") (pintype "bidirectional"))
    )
    (net (code "139") (name "unconnected-(U$19-1-PadP$1)") (class "Default")
      (node (ref "U$19") (pin "P$1") (pinfunction "1_P$1") (pintype "bidirectional"))
    )
    (net (code "140") (name "unconnected-(U$19-2-PadP$2)") (class "Default")
      (node (ref "U$19") (pin "P$2") (pinfunction "2_P$2") (pintype "bidirectional"))
    )
    (net (code "141") (name "unconnected-(U$19-3-PadP$3)") (class "Default")
      (node (ref "U$19") (pin "P$3") (pinfunction "3_P$3") (pintype "bidirectional"))
    )
    (net (code "142") (name "unconnected-(U$20-Pad1)") (class "Default")
      (node (ref "U$20") (pin "1") (pinfunction "1_1") (pintype "bidirectional"))
    )
    (net (code "143") (name "unconnected-(U$20-Pad2)") (class "Default")
      (node (ref "U$20") (pin "2") (pinfunction "2_2") (pintype "bidirectional"))
    )
    (net (code "144") (name "unconnected-(U$20-Pad3)") (class "Default")
      (node (ref "U$20") (pin "3") (pinfunction "3_3") (pintype "bidirectional"))
    )
    (net (code "145") (name "unconnected-(U$20-Pad4)") (class "Default")
      (node (ref "U$20") (pin "4") (pinfunction "4_4") (pintype "bidirectional"))
    )
    (net (code "146") (name "unconnected-(U$20-Pad5)") (class "Default")
      (node (ref "U$20") (pin "5") (pinfunction "5_5") (pintype "bidirectional"))
    )
    (net (code "147") (name "unconnected-(U1-NC-Pad7)") (class "Default")
      (node (ref "U1") (pin "7") (pinfunction "NC_7") (pintype "passive"))
    )
    (net (code "148") (name "unconnected-(U1-NC_2-Pad2)") (class "Default")
      (node (ref "U1") (pin "2") (pinfunction "NC_2_2") (pintype "passive"))
    )
    (net (code "149") (name "unconnected-(U1-NC_3-Pad6)") (class "Default")
      (node (ref "U1") (pin "6") (pinfunction "NC_3_6") (pintype "passive"))
    )
    (net (code "150") (name "unconnected-(U1-NR{slash}FB-Pad3)") (class "Default")
      (node (ref "U1") (pin "3") (pinfunction "NR/FB_3") (pintype "bidirectional"))
    )
    (net (code "151") (name "unconnected-(U2-NC-Pad8)") (class "Default")
      (node (ref "U2") (pin "8") (pinfunction "NC_8") (pintype "passive"))
    )
    (net (code "152") (name "unconnected-(U2-NC_2-Pad5)") (class "Default")
      (node (ref "U2") (pin "5") (pinfunction "NC_2_5") (pintype "passive"))
    )
    (net (code "153") (name "unconnected-(U3-RIN4+-Pad7)") (class "Default")
      (node (ref "U3") (pin "7") (pinfunction "RIN4+_7") (pintype "passive"))
    )
    (net (code "154") (name "unconnected-(U3-RIN4-Pad8)") (class "Default")
      (node (ref "U3") (pin "8") (pinfunction "RIN4_8") (pintype "passive"))
    )
    (net (code "155") (name "unconnected-(U3-ROUT4-Pad10)") (class "Default")
      (node (ref "U3") (pin "10") (pinfunction "ROUT4_10") (pintype "passive"))
    )
    (net (code "156") (name "unconnected-(U4-PWRGD-Pad6)") (class "Default")
      (node (ref "U4") (pin "6") (pinfunction "PWRGD_6") (pintype "output"))
    )
  )
)
